# design.net
KiCad netlist of a schematic drawn in Altium Designer
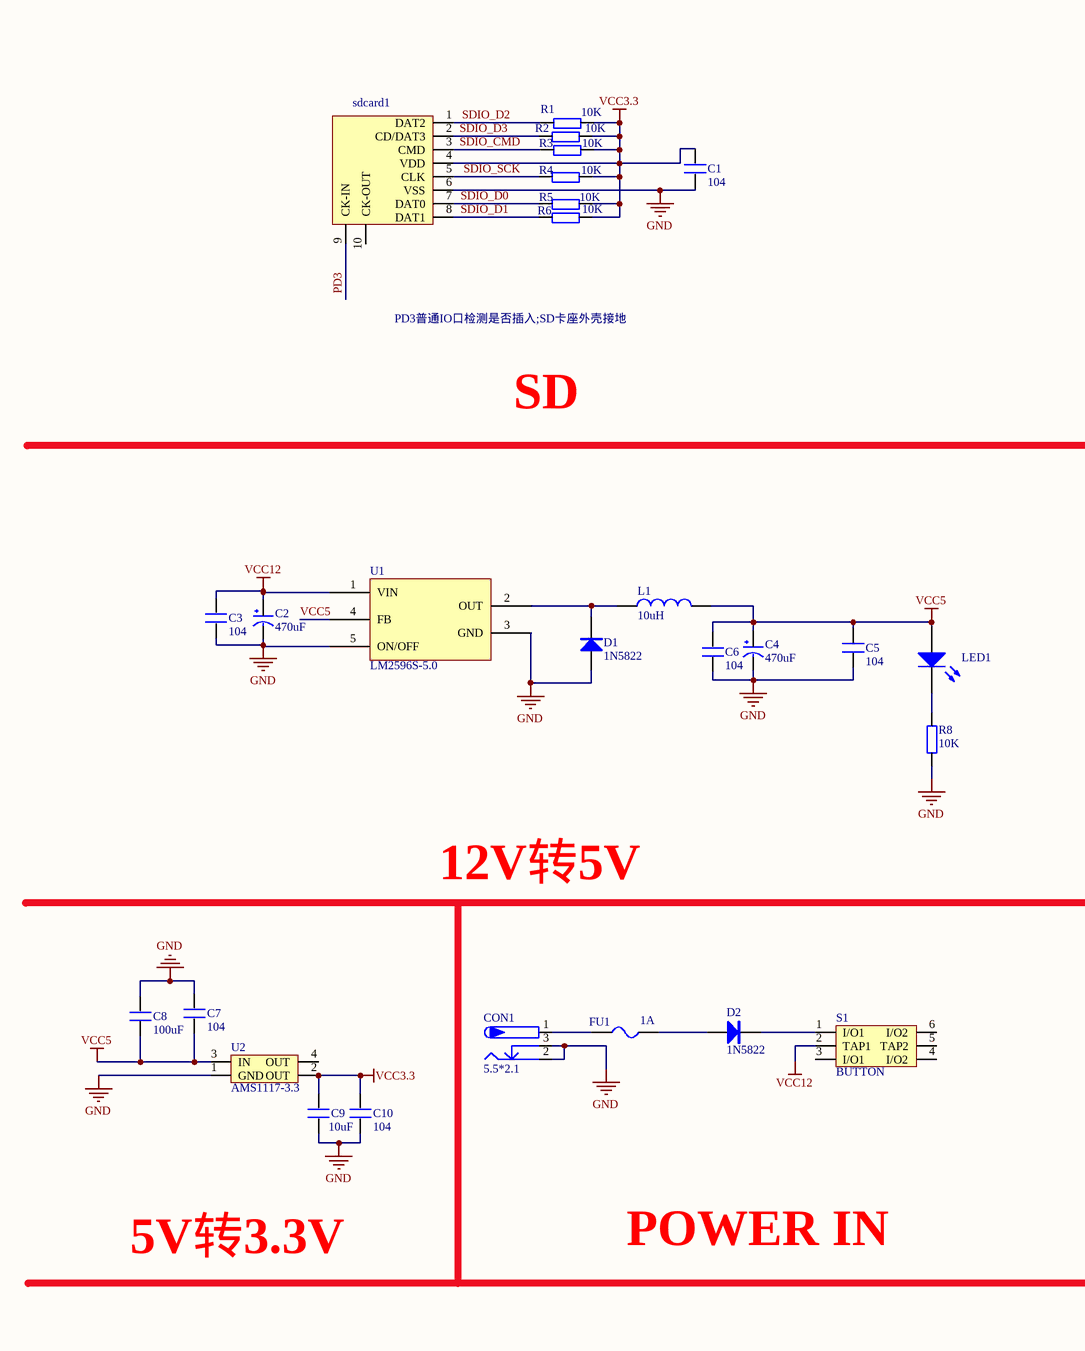
[diagram p0: 门禁改.SchDoc, top left]
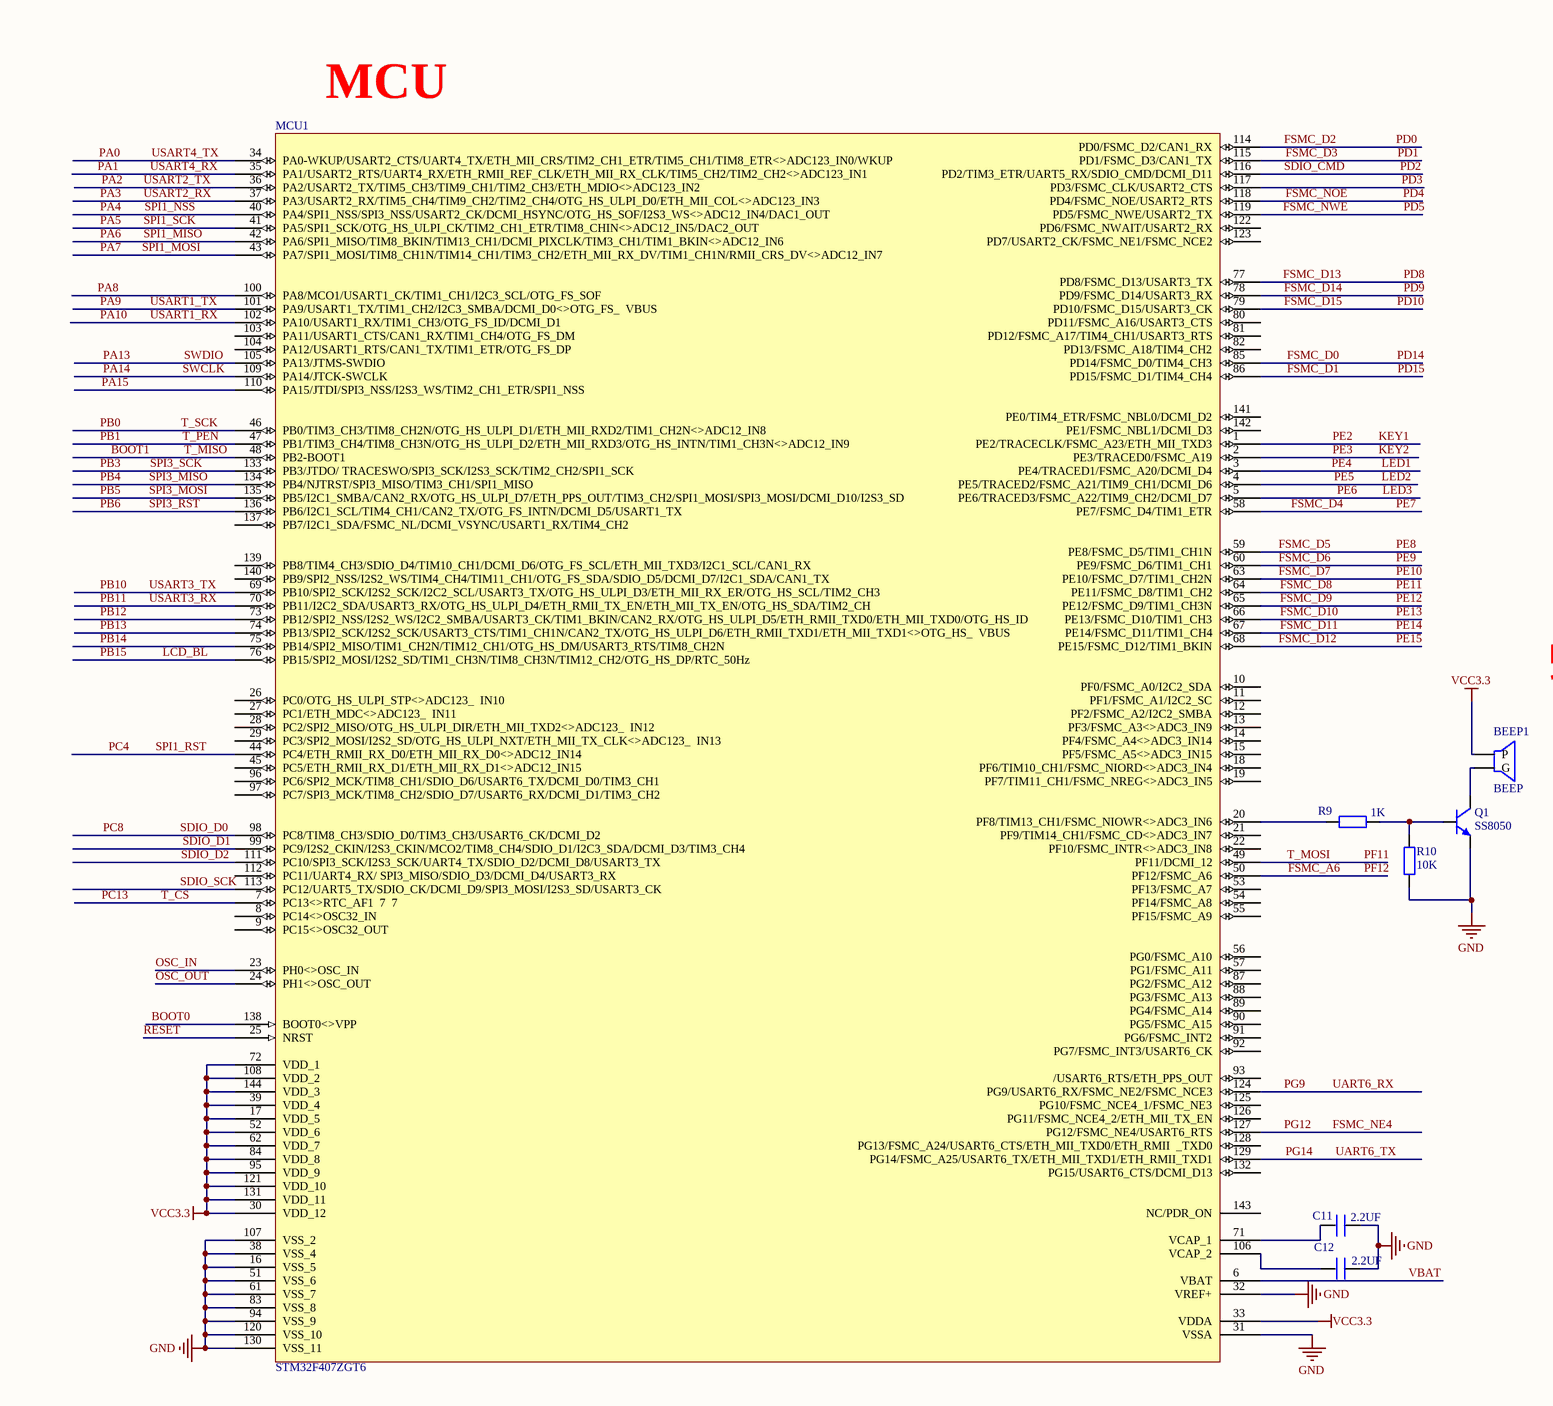
[diagram p1: 门禁改.SchDoc, top middle]
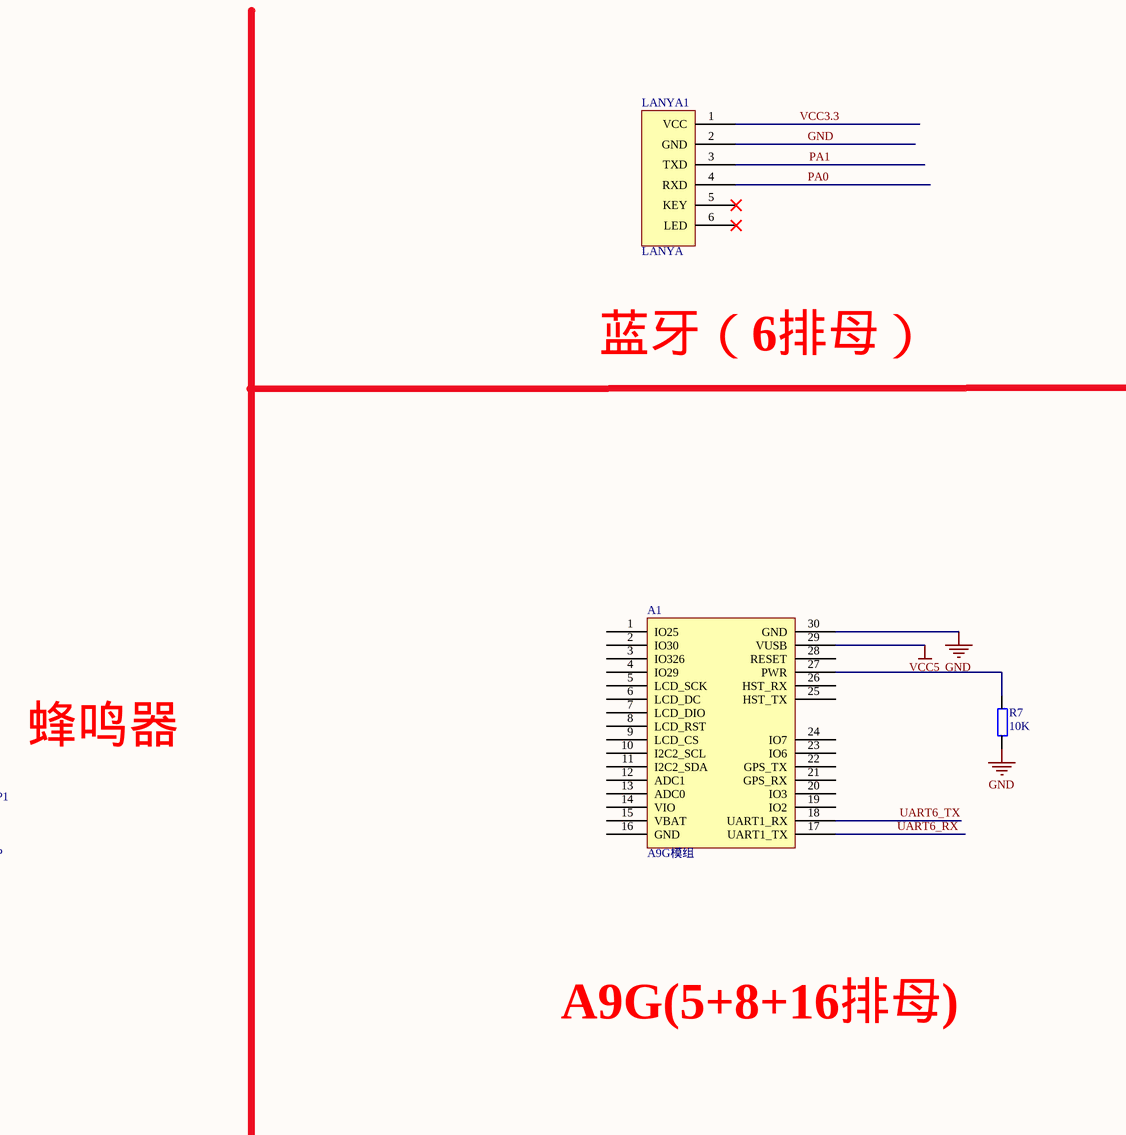
[diagram p2: 门禁改.SchDoc, top right]
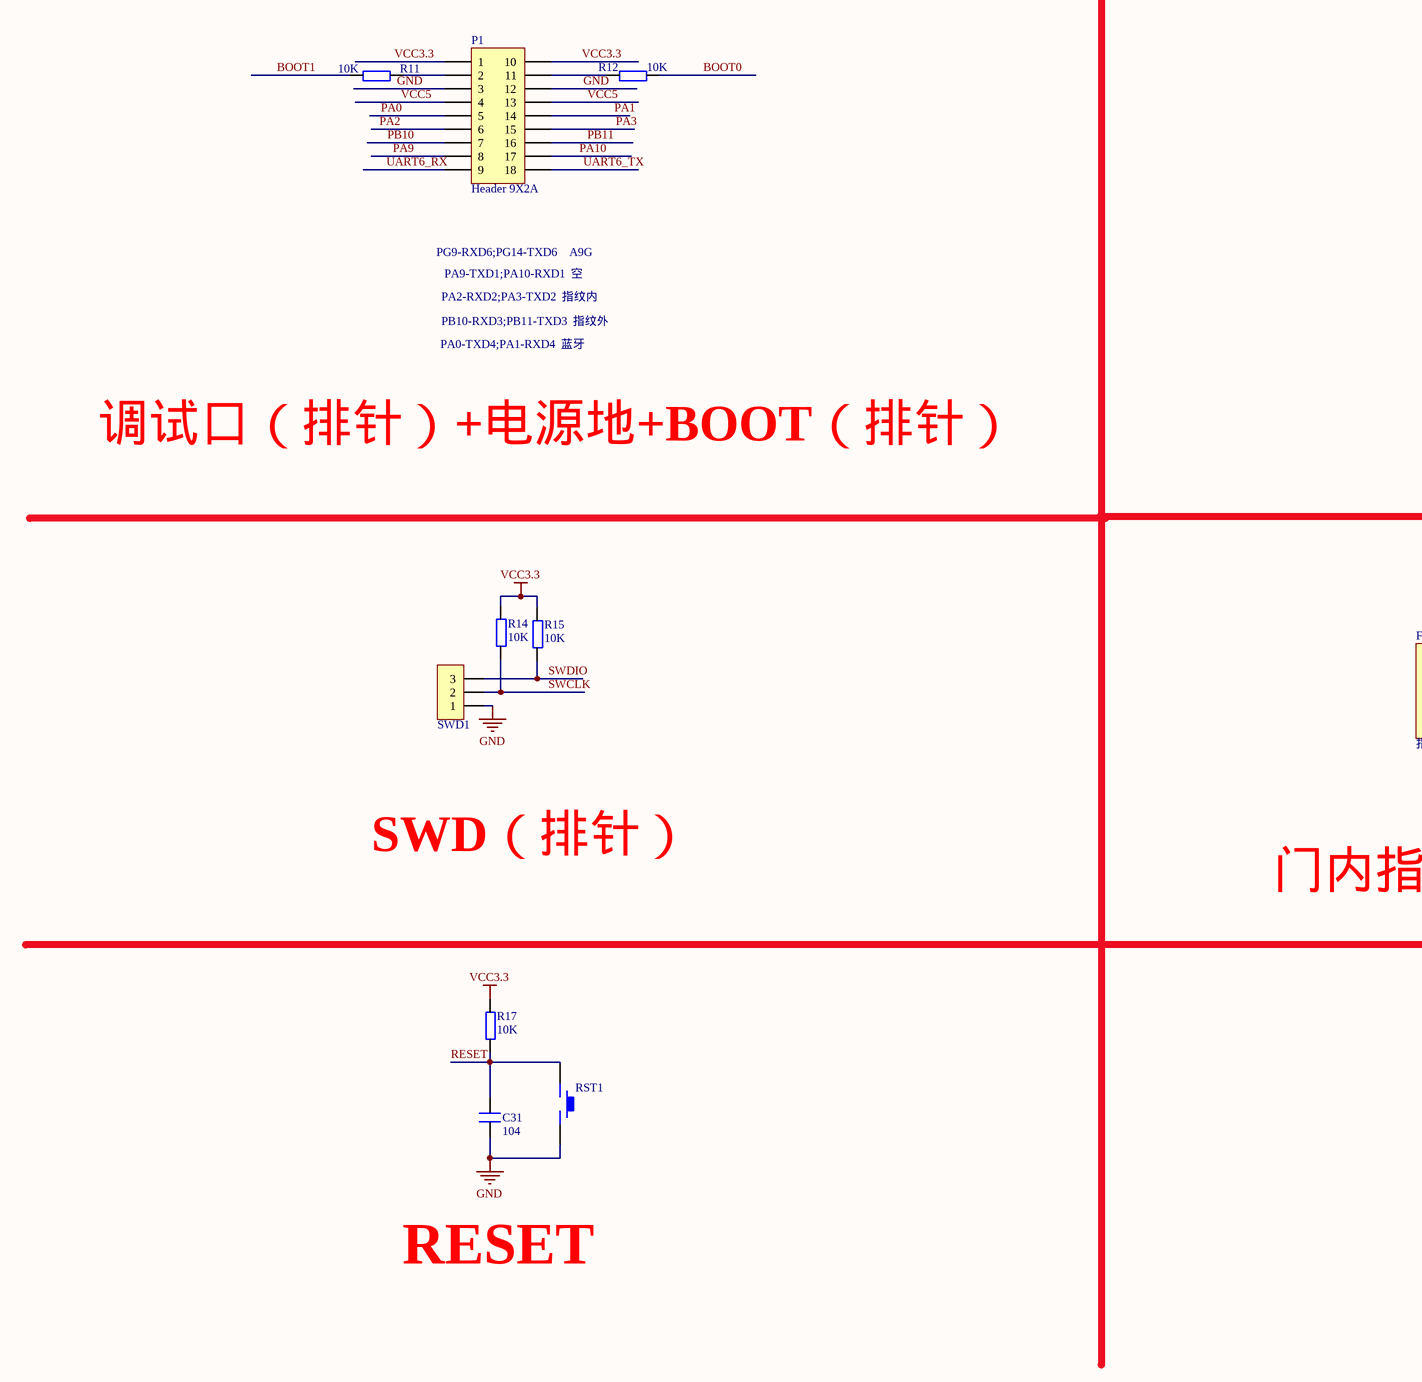
[diagram p3: 门禁改.SchDoc, bottom left]
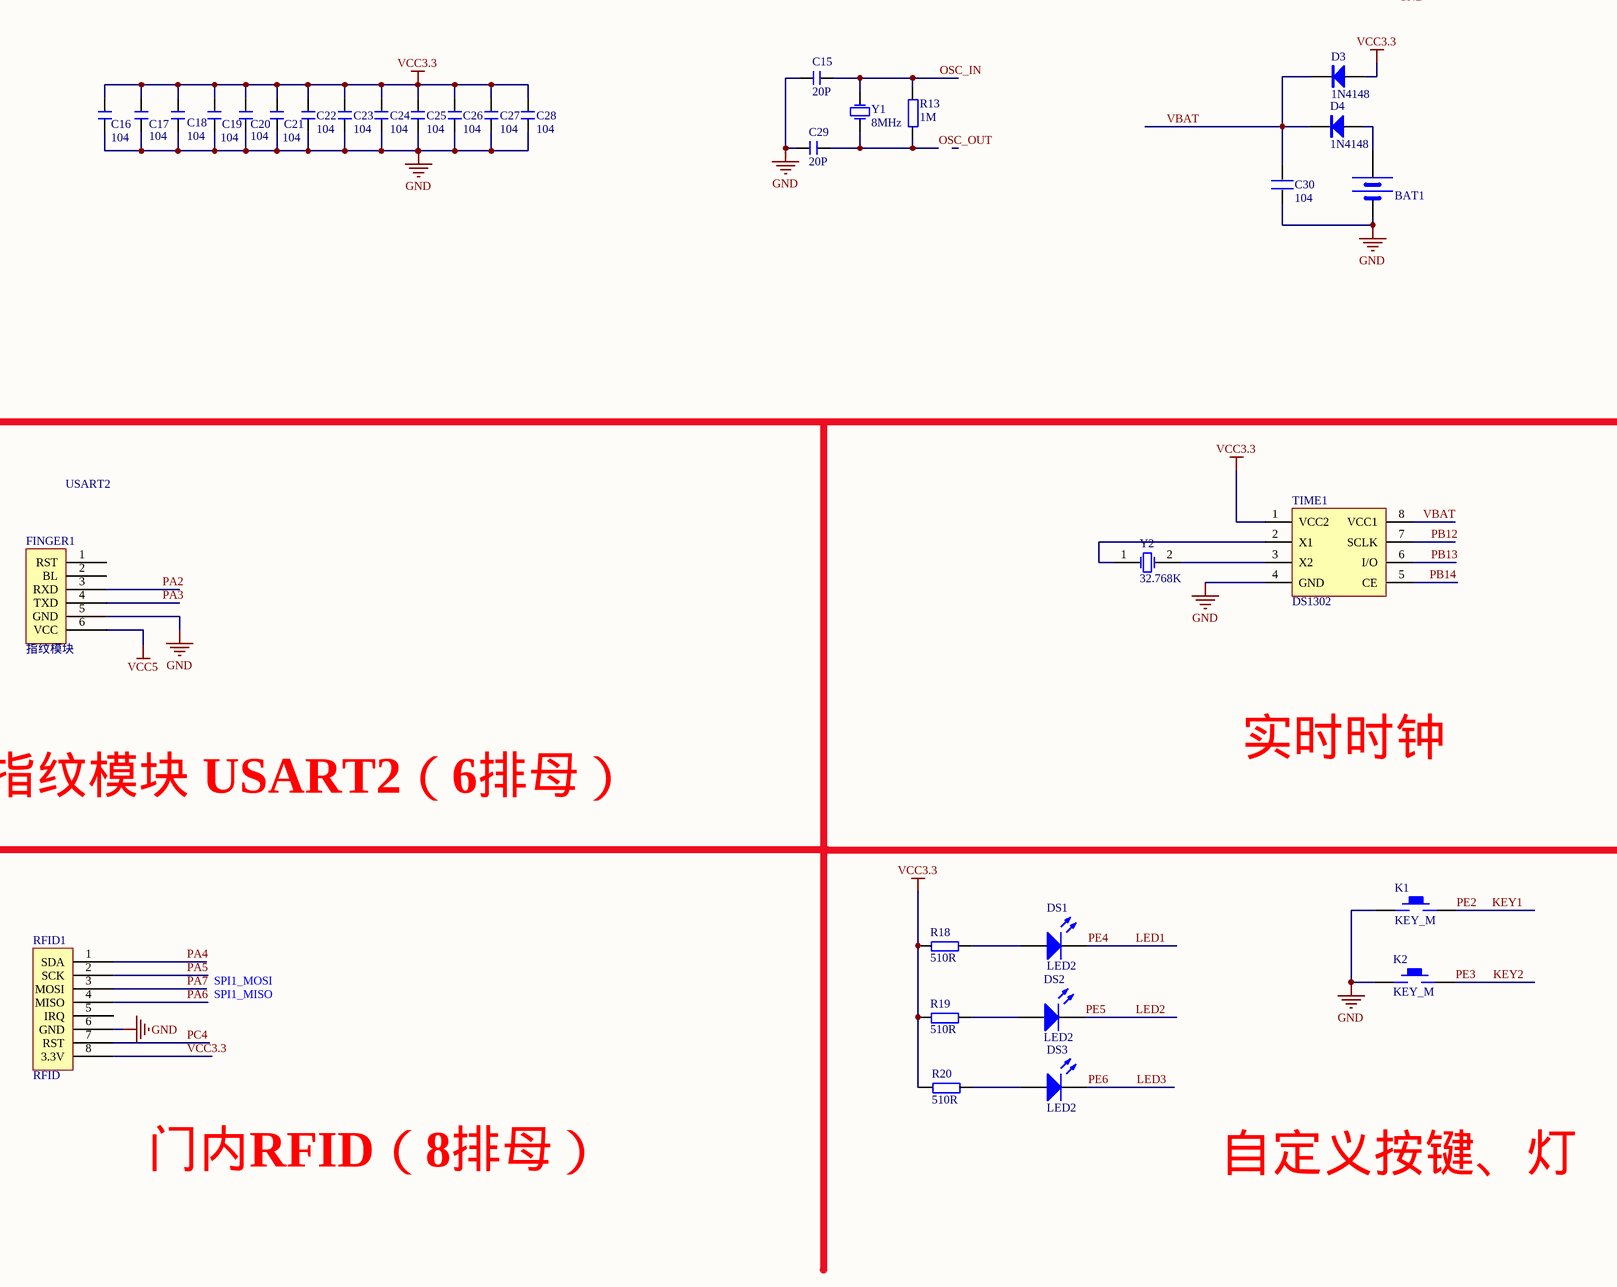
[diagram p4: 门禁改.SchDoc, bottom middle]
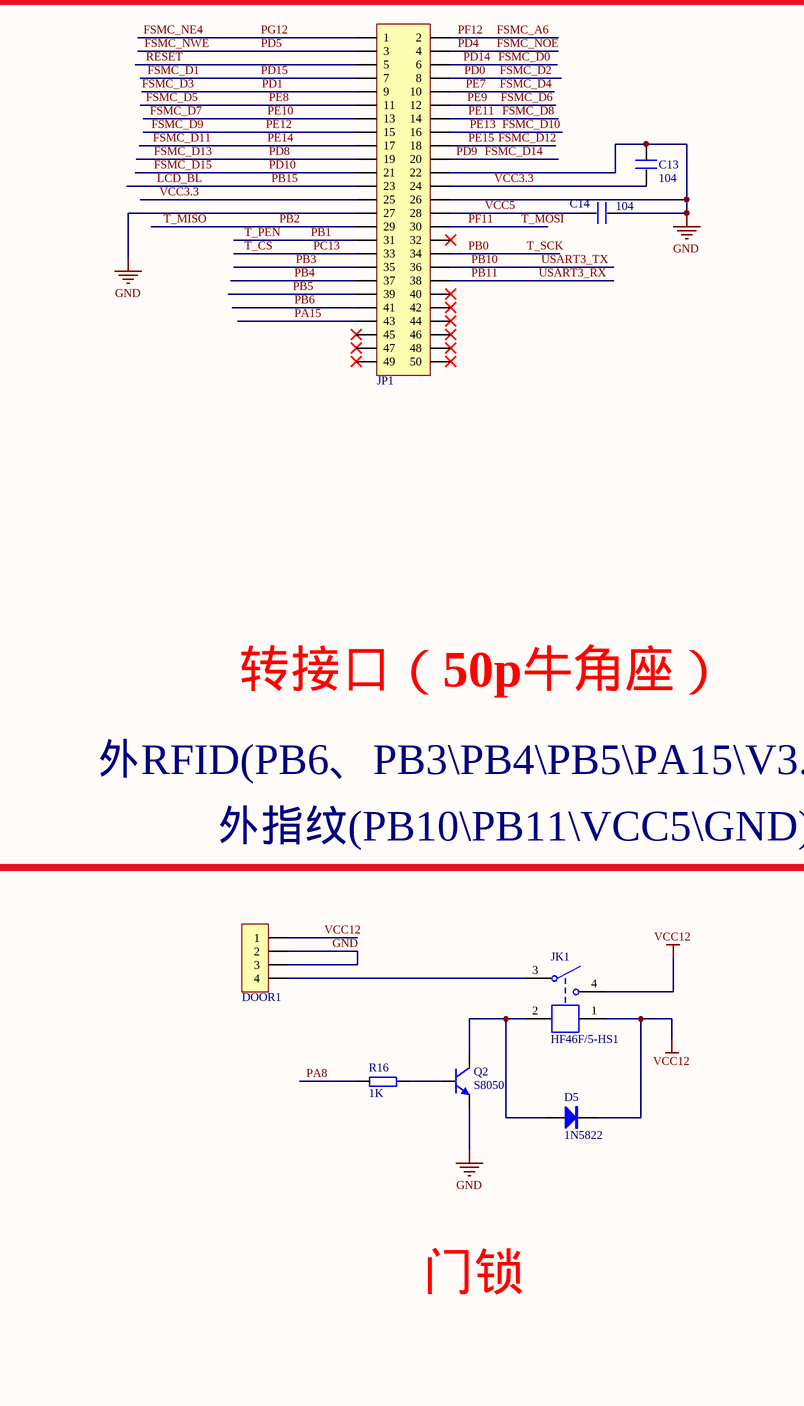
[diagram p5: 门禁改.SchDoc, bottom right]

(export (version "E")
  (design (tool "Eeschema 10.0.6"))
  (components
    (comp (ref "A1") (value "A9G模组") (footprint "A9G") (libsource (lib "A9G模组") (part "A9G模组")))
    (comp (ref "BAT1") (value "BATT") (footprint "BATMAX") (libsource (lib "门禁系统") (part "BAT")))
    (comp (ref "BEEP1") (value "BEEP") (footprint "BUZZ") (libsource (lib "门禁系统") (part "BEEP")))
    (comp (ref "C1") (value "104") (footprint "0805") (libsource (lib "Explorer STM32F407封装库") (part "C")))
    (comp (ref "C2") (value "470uF") (footprint "CM F(10*10.2)") (libsource (lib "门禁系统") (part "CAP")))
    (comp (ref "C3") (value "104") (footprint "0805") (libsource (lib "门禁系统") (part "C")))
    (comp (ref "C4") (value "470uF") (footprint "CM F(10*10.2)") (libsource (lib "门禁系统") (part "CAP")))
    (comp (ref "C5") (value "104") (footprint "0805") (libsource (lib "门禁系统") (part "C")))
    (comp (ref "C6") (value "104") (footprint "0805") (libsource (lib "门禁系统") (part "C")))
    (comp (ref "C7") (value "104") (footprint "0603P") (libsource (lib "Explorer STM32F407封装库") (part "C")))
    (comp (ref "C8")
      (value "100uF")
      (footprint "CM D(6.3*7.7)")
      (libsource (lib "Explorer STM32F407封装库") (part "C"))
    )
    (comp (ref "C9") (value "10uF") (footprint "0603P") (libsource (lib "Explorer STM32F407封装库") (part "C")))
    (comp (ref "C10") (value "104") (footprint "0603P") (libsource (lib "Explorer STM32F407封装库") (part "C")))
    (comp (ref "C11")
      (value "2.2UF")
      (footprint "0805")
      (libsource (lib "Explorer STM32F407封装库_SCH") (part "C_1"))
    )
    (comp (ref "C12")
      (value "2.2UF")
      (footprint "0805")
      (libsource (lib "Explorer STM32F407封装库_SCH") (part "C_1"))
    )
    (comp (ref "C13") (value "104") (footprint "0805") (libsource (lib "Explorer STM32F407封装库") (part "C")))
    (comp (ref "C14") (value "104") (footprint "0805") (libsource (lib "Explorer STM32F407封装库") (part "C")))
    (comp (ref "C15")
      (value "20P")
      (footprint "0805")
      (description "无极性贴片电容")
      (fields (field (name "版权归属") "源创客"))
      (libsource (lib "3.1   - 电阻-电容-电感") (part "C"))
    )
    (comp (ref "C16")
      (value "104")
      (footprint "0805")
      (description "无极性贴片电容")
      (fields (field (name "版权归属") "源创客"))
      (libsource (lib "3.1   - 电阻-电容-电感") (part "C"))
    )
    (comp (ref "C17")
      (value "104")
      (footprint "0805")
      (description "无极性贴片电容")
      (fields (field (name "版权归属") "源创客"))
      (libsource (lib "3.1   - 电阻-电容-电感") (part "C"))
    )
    (comp (ref "C18")
      (value "104")
      (footprint "0805")
      (description "无极性贴片电容")
      (fields (field (name "版权归属") "源创客"))
      (libsource (lib "3.1   - 电阻-电容-电感") (part "C"))
    )
    (comp (ref "C19")
      (value "104")
      (footprint "0805")
      (description "无极性贴片电容")
      (fields (field (name "版权归属") "源创客"))
      (libsource (lib "3.1   - 电阻-电容-电感") (part "C"))
    )
    (comp (ref "C20")
      (value "104")
      (footprint "0805")
      (description "无极性贴片电容")
      (fields (field (name "版权归属") "源创客"))
      (libsource (lib "3.1   - 电阻-电容-电感") (part "C"))
    )
    (comp (ref "C21")
      (value "104")
      (footprint "0805")
      (description "无极性贴片电容")
      (fields (field (name "版权归属") "源创客"))
      (libsource (lib "3.1   - 电阻-电容-电感") (part "C"))
    )
    (comp (ref "C22")
      (value "104")
      (footprint "0805")
      (description "无极性贴片电容")
      (fields (field (name "版权归属") "源创客"))
      (libsource (lib "3.1   - 电阻-电容-电感") (part "C"))
    )
    (comp (ref "C23")
      (value "104")
      (footprint "0805")
      (description "无极性贴片电容")
      (fields (field (name "版权归属") "源创客"))
      (libsource (lib "3.1   - 电阻-电容-电感") (part "C"))
    )
    (comp (ref "C24")
      (value "104")
      (footprint "0805")
      (description "无极性贴片电容")
      (fields (field (name "版权归属") "源创客"))
      (libsource (lib "3.1   - 电阻-电容-电感") (part "C"))
    )
    (comp (ref "C25")
      (value "104")
      (footprint "0805")
      (description "无极性贴片电容")
      (fields (field (name "版权归属") "源创客"))
      (libsource (lib "3.1   - 电阻-电容-电感") (part "C"))
    )
    (comp (ref "C26")
      (value "104")
      (footprint "0805")
      (description "无极性贴片电容")
      (fields (field (name "版权归属") "源创客"))
      (libsource (lib "3.1   - 电阻-电容-电感") (part "C"))
    )
    (comp (ref "C27")
      (value "104")
      (footprint "0805")
      (description "无极性贴片电容")
      (fields (field (name "版权归属") "源创客"))
      (libsource (lib "3.1   - 电阻-电容-电感") (part "C"))
    )
    (comp (ref "C28")
      (value "104")
      (footprint "0805")
      (description "无极性贴片电容")
      (fields (field (name "版权归属") "源创客"))
      (libsource (lib "3.1   - 电阻-电容-电感") (part "C"))
    )
    (comp (ref "C29")
      (value "20P")
      (footprint "0805")
      (description "无极性贴片电容")
      (fields (field (name "版权归属") "源创客"))
      (libsource (lib "3.1   - 电阻-电容-电感") (part "C"))
    )
    (comp (ref "C30") (value "104") (footprint "0805") (libsource (lib "门禁") (part "C")))
    (comp (ref "C31")
      (value "104")
      (footprint "0805")
      (libsource (lib "Explorer STM32F407封装库_SCH") (part "C"))
    )
    (comp (ref "CON1")
      (value "5.5*2.1")
      (footprint "DC-005")
      (description "低压电源接口")
      (fields (field (name "版权归属") "源创客"))
      (libsource (lib "4.1   - 接口类") (part "P-DC"))
    )
    (comp (ref "D1")
      (value "1N5822")
      (footprint "DIODE_3*5.3")
      (description "高速开关二极管")
      (fields (field (name "版权归属") "源创客"))
      (libsource (lib "8.1   - 二极管-整流桥") (part "1N4148"))
    )
    (comp (ref "D2")
      (value "1N5822")
      (footprint "DIODE_3*5.3")
      (description "高速开关二极管")
      (fields (field (name "版权归属") "源创客"))
      (libsource (lib "8.1   - 二极管-整流桥") (part "1N4148"))
    )
    (comp (ref "D3")
      (value "1N4148")
      (footprint "DIODE_3*5.3")
      (description "高速开关二极管")
      (fields (field (name "版权归属") "源创客"))
      (libsource (lib "门禁") (part "1N4148"))
    )
    (comp (ref "D4")
      (value "1N4148")
      (footprint "DIODE_3*5.3")
      (description "高速开关二极管")
      (fields (field (name "版权归属") "源创客"))
      (libsource (lib "门禁") (part "1N4148"))
    )
    (comp (ref "D5")
      (value "1N5822")
      (footprint "DIODE_3*5.3")
      (description "高速开关二极管")
      (fields (field (name "版权归属") "源创客"))
      (libsource (lib "8.1   - 二极管-整流桥") (part "1N4148"))
    )
    (comp (ref "DOOR1")
      (value "HDR-1X4")
      (footprint "XH2.54-WI-4P")
      (description "4P接插件")
      (fields (field (name "版权归属") "源创客"))
      (libsource (lib "4.5   - 接插件-脚距2.54") (part "Header 4"))
    )
    (comp (ref "DS1")
      (value "LED2")
      (footprint "SMDLED")
      (description "Typical RED, GREEN, YELLOW, AMBER GaAs LED")
      (fields (field (name "PUBLISHER") "*"))
      (libsource (lib "Explorer STM32F407封装库_SCH") (part "LED2"))
    )
    (comp (ref "DS2")
      (value "LED2")
      (footprint "SMDLED")
      (description "Typical RED, GREEN, YELLOW, AMBER GaAs LED")
      (fields (field (name "PUBLISHER") "*"))
      (libsource (lib "Explorer STM32F407封装库_SCH") (part "LED2"))
    )
    (comp (ref "DS3")
      (value "LED2")
      (footprint "SMDLED")
      (description "Typical RED, GREEN, YELLOW, AMBER GaAs LED")
      (fields (field (name "PUBLISHER") "*"))
      (libsource (lib "Explorer STM32F407封装库_SCH") (part "LED2"))
    )
    (comp (ref "FINGER1") (value "指纹模块") (footprint "指纹") (libsource (lib "Schlib1") (part "指纹模块")))
    (comp (ref "FU1")
      (value "1A")
      (footprint "FU 1812")
      (description "贴片保险丝")
      (fields (field (name "版权归属") "源创客"))
      (libsource (lib "10.1 - 保险丝-晶振") (part "FU"))
    )
    (comp (ref "JK1")
      (value "HF46F/5-HS1")
      (footprint "HF46-xx-HS1")
      (description "5V一组常开")
      (fields (field (name "版权归属") "源创客"))
      (libsource (lib "7.1   - 继电器") (part "HF46F/5-HS1"))
    )
    (comp (ref "JP1")
      (value "Header 2X25")
      (footprint "IDC2.54-LI-2x25P")
      (description "25*2P接插件")
      (fields (field (name "版权归属") "源创客"))
      (libsource (lib "4.5   - 接插件-脚距2.54") (part "Header 25X2"))
    )
    (comp (ref "K1")
      (value "KEY_M")
      (footprint "KEY_M")
      (libsource (lib "Explorer STM32F407封装库_SCH") (part "KEY_M"))
    )
    (comp (ref "K2")
      (value "KEY_M")
      (footprint "KEY_M")
      (libsource (lib "Explorer STM32F407封装库_SCH") (part "KEY_M"))
    )
    (comp (ref "L1")
      (value "10uH")
      (footprint "0805")
      (description "小功率贴片电感")
      (fields (field (name "版权归属") "源创客"))
      (libsource (lib "3.1   - 电阻-电容-电感") (part "L"))
    )
    (comp (ref "LANYA1") (value "LANYA") (footprint "蓝牙") (libsource (lib "Schlib1") (part "蓝牙模块")))
    (comp (ref "LED1")
      (value "LED1")
      (footprint "SMDLED")
      (description "Typical RED, GREEN, YELLOW, AMBER GaAs LED")
      (fields (field (name "PUBLISHER") "Altium Limited"))
      (libsource (lib "门禁系统") (part "LED2"))
    )
    (comp (ref "MCU1")
      (value "STM32F407ZGT6")
      (footprint "LQFP144")
      (libsource (lib "STM32F407 ") (part "STM32F407ZGT6"))
    )
    (comp (ref "P1")
      (value "Header 9X2A")
      (footprint "HDR2X9_CEN")
      (description "Header, 9-Pin, Dual row")
      (fields (field (name "PUBLISHER") "Altium Limited"))
      (libsource (lib "Miscellaneous Connectors") (part "Header 9X2A"))
    )
    (comp (ref "Q1")
      (value "SS8050")
      (footprint "SOT23-3N")
      (description "高频放大-NPN型")
      (fields (field (name "版权归属") "源创客"))
      (libsource (lib "6.2   - 三极管") (part "8050-SMD"))
    )
    (comp (ref "Q2")
      (value "S8050")
      (footprint "SOT23-3N")
      (description "高频放大-NPN型")
      (fields (field (name "版权归属") "源创客"))
      (libsource (lib "6.2   - 三极管") (part "8050-SMD"))
    )
    (comp (ref "R1") (value "10K") (footprint "0805") (libsource (lib "Explorer STM32F407封装库") (part "R")))
    (comp (ref "R2") (value "10K") (footprint "0805") (libsource (lib "Explorer STM32F407封装库") (part "R")))
    (comp (ref "R3") (value "10K") (footprint "0805") (libsource (lib "Explorer STM32F407封装库") (part "R")))
    (comp (ref "R4") (value "10K") (footprint "0805") (libsource (lib "Explorer STM32F407封装库") (part "R")))
    (comp (ref "R5") (value "10K") (footprint "0805") (libsource (lib "Explorer STM32F407封装库") (part "R")))
    (comp (ref "R6") (value "10K") (footprint "0805") (libsource (lib "Explorer STM32F407封装库") (part "R")))
    (comp (ref "R7") (value "10K") (footprint "0805") (libsource (lib "门禁") (part "R")))
    (comp (ref "R8") (value "10K") (footprint "0805") (libsource (lib "门禁系统") (part "R")))
    (comp (ref "R9")
      (value "1K")
      (footprint "0805")
      (description "贴片电阻")
      (fields (field (name "版权归属") "源创客"))
      (libsource (lib "3.1   - 电阻-电容-电感") (part "R"))
    )
    (comp (ref "R10")
      (value "10K")
      (footprint "0805")
      (description "贴片电阻")
      (fields (field (name "版权归属") "源创客"))
      (libsource (lib "3.1   - 电阻-电容-电感") (part "R"))
    )
    (comp (ref "R11") (value "10K") (footprint "0805") (libsource (lib "Explorer STM32F407封装库") (part "R")))
    (comp (ref "R12")
      (value "10K")
      (footprint "0805")
      (libsource (lib "Explorer STM32F407封装库_SCH") (part "R"))
    )
    (comp (ref "R13") (value "1M") (footprint "0805") (libsource (lib "门禁系统") (part "R")))
    (comp (ref "R14") (value "10K") (footprint "0805") (libsource (lib "WarShip V3 STM32103封装库") (part "R")))
    (comp (ref "R15") (value "10K") (footprint "0805") (libsource (lib "WarShip V3 STM32103封装库") (part "R")))
    (comp (ref "R16")
      (value "1K")
      (footprint "0805")
      (libsource (lib "Explorer STM32F407封装库_SCH") (part "R"))
    )
    (comp (ref "R17")
      (value "10K")
      (footprint "0805")
      (libsource (lib "Explorer STM32F407封装库_SCH") (part "R"))
    )
    (comp (ref "R18")
      (value "510R")
      (footprint "0805")
      (libsource (lib "Explorer STM32F407封装库_SCH") (part "R"))
    )
    (comp (ref "R19")
      (value "510R")
      (footprint "0805")
      (libsource (lib "Explorer STM32F407封装库_SCH") (part "R"))
    )
    (comp (ref "R20")
      (value "510R")
      (footprint "0805")
      (libsource (lib "Explorer STM32F407封装库_SCH") (part "R"))
    )
    (comp (ref "RFID1") (value "RFID") (footprint "RFID") (libsource (lib "Schlib1") (part "RC522")))
    (comp (ref "RST1") (value "~") (footprint "KEY_M") (libsource (lib "") (part "KEY_M_1")))
    (comp (ref "S1") (value "BUTTON") (footprint "BTN8.5*8.5") (libsource (lib "门禁系统") (part "BUTTON")))
    (comp (ref "sdcard1")
      (value "sdIO-sdcard")
      (footprint "sdcard_2")
      (libsource (lib "门禁系统") (part "sdIO-sdcard"))
    )
    (comp (ref "SWD1")
      (value "HDR-1X3")
      (footprint "HDR2.54-LI-3P")
      (description "3P接插件")
      (fields (field (name "版权归属") "源创客"))
      (libsource (lib "4.10 - 接插件-脚距5.08") (part "Header 3"))
    )
    (comp (ref "TIME1")
      (value "DS1302")
      (footprint "SOP8_N")
      (description "实时时钟芯片")
      (fields (field (name "版权归属") "源创客"))
      (libsource (lib "1.1   - IC芯片") (part "DS1302"))
    )
    (comp (ref "U1")
      (value "LM2596S-5.0")
      (footprint "TO263-5A")
      (description "LM2576S-5.0")
      (libsource (lib "Schlib1") (part "Component_1"))
    )
    (comp (ref "U2") (value "AMS1117-3.3") (footprint "AMS1117") (libsource (lib "门禁系统") (part "AMS1117")))
    (comp (ref "Y1")
      (value "8MHz")
      (footprint "XTAL_T")
      (description "Crystal Oscillator")
      (fields (field (name "PUBLISHER") "Altium Limited"))
      (libsource (lib "门禁系统") (part "XTAL_2"))
    )
    (comp (ref "Y2")
      (value "32.768K")
      (footprint "XTAL32")
      (description "Crystal Oscillator")
      (fields (field (name "PUBLISHER") "Altium Limited"))
      (libsource (lib "门禁系统") (part "XTAL_1"))
    )
  )
  (nets
    (net (code "2") (name "/BOOT0") (class "Default")
      (node (ref "MCU1") (pin "138") (pinfunction "BOOT0<>VPP_138") (pintype "input"))
      (node (ref "R12") (pin "2") (pintype "passive"))
    )
    (net (code "3") (name "/BOOT1") (class "Default")
      (node (ref "JP1") (pin "29") (pinfunction "29_29") (pintype "passive"))
      (node (ref "MCU1") (pin "48") (pinfunction "PB2-BOOT1_48") (pintype "bidirectional"))
      (node (ref "R11") (pin "1") (pintype "passive"))
    )
    (net (code "4") (name "/FSMC_A6") (class "Default")
      (node (ref "JP1") (pin "2") (pinfunction "2_2") (pintype "passive"))
      (node (ref "MCU1") (pin "50") (pinfunction "PF12/FSMC_A6_50") (pintype "bidirectional"))
    )
    (net (code "5") (name "/FSMC_D0") (class "Default")
      (node (ref "JP1") (pin "6") (pinfunction "6_6") (pintype "passive"))
      (node (ref "MCU1") (pin "85") (pinfunction "PD14/FSMC_D0/TIM4_CH3_85") (pintype "bidirectional"))
    )
    (net (code "6") (name "/FSMC_D1") (class "Default")
      (node (ref "JP1") (pin "7") (pinfunction "7_7") (pintype "passive"))
      (node (ref "MCU1") (pin "86") (pinfunction "PD15/FSMC_D1/TIM4_CH4_86") (pintype "bidirectional"))
    )
    (net (code "7") (name "/FSMC_D2") (class "Default")
      (node (ref "JP1") (pin "8") (pinfunction "8_8") (pintype "passive"))
      (node (ref "MCU1") (pin "114") (pinfunction "PD0/FSMC_D2/CAN1_RX_114") (pintype "bidirectional"))
    )
    (net (code "8") (name "/FSMC_D3") (class "Default")
      (node (ref "JP1") (pin "9") (pinfunction "9_9") (pintype "passive"))
      (node (ref "MCU1") (pin "115") (pinfunction "PD1/FSMC_D3/CAN1_TX_115") (pintype "bidirectional"))
    )
    (net (code "9") (name "/FSMC_D4") (class "Default")
      (node (ref "JP1") (pin "10") (pinfunction "10_10") (pintype "passive"))
      (node (ref "MCU1") (pin "58") (pinfunction "PE7/FSMC_D4/TIM1_ETR_58") (pintype "bidirectional"))
    )
    (net (code "10") (name "/FSMC_D5") (class "Default")
      (node (ref "JP1") (pin "11") (pinfunction "11_11") (pintype "passive"))
      (node (ref "MCU1") (pin "59") (pinfunction "PE8/FSMC_D5/TIM1_CH1N_59") (pintype "bidirectional"))
    )
    (net (code "11") (name "/FSMC_D6") (class "Default")
      (node (ref "JP1") (pin "12") (pinfunction "12_12") (pintype "passive"))
      (node (ref "MCU1") (pin "60") (pinfunction "PE9/FSMC_D6/TIM1_CH1_60") (pintype "bidirectional"))
    )
    (net (code "12") (name "/FSMC_D7") (class "Default")
      (node (ref "JP1") (pin "13") (pinfunction "13_13") (pintype "passive"))
      (node (ref "MCU1") (pin "63") (pinfunction "PE10/FSMC_D7/TIM1_CH2N_63") (pintype "bidirectional"))
    )
    (net (code "13") (name "/FSMC_D8") (class "Default")
      (node (ref "JP1") (pin "14") (pinfunction "14_14") (pintype "passive"))
      (node (ref "MCU1") (pin "64") (pinfunction "PE11/FSMC_D8/TIM1_CH2_64") (pintype "bidirectional"))
    )
    (net (code "14") (name "/FSMC_D9") (class "Default")
      (node (ref "JP1") (pin "15") (pinfunction "15_15") (pintype "passive"))
      (node (ref "MCU1") (pin "65") (pinfunction "PE12/FSMC_D9/TIM1_CH3N_65") (pintype "bidirectional"))
    )
    (net (code "15") (name "/FSMC_D10") (class "Default")
      (node (ref "JP1") (pin "16") (pinfunction "16_16") (pintype "passive"))
      (node (ref "MCU1") (pin "66") (pinfunction "PE13/FSMC_D10/TIM1_CH3_66") (pintype "bidirectional"))
    )
    (net (code "16") (name "/FSMC_D11") (class "Default")
      (node (ref "JP1") (pin "17") (pinfunction "17_17") (pintype "passive"))
      (node (ref "MCU1") (pin "67") (pinfunction "PE14/FSMC_D11/TIM1_CH4_67") (pintype "bidirectional"))
    )
    (net (code "17") (name "/FSMC_D12") (class "Default")
      (node (ref "JP1") (pin "18") (pinfunction "18_18") (pintype "passive"))
      (node (ref "MCU1") (pin "68") (pinfunction "PE15/FSMC_D12/TIM1_BKIN_68") (pintype "bidirectional"))
    )
    (net (code "18") (name "/FSMC_D13") (class "Default")
      (node (ref "JP1") (pin "19") (pinfunction "19_19") (pintype "passive"))
      (node (ref "MCU1") (pin "77") (pinfunction "PD8/FSMC_D13/USART3_TX_77") (pintype "bidirectional"))
    )
    (net (code "19") (name "/FSMC_D14") (class "Default")
      (node (ref "JP1") (pin "20") (pinfunction "20_20") (pintype "passive"))
      (node (ref "MCU1") (pin "78") (pinfunction "PD9/FSMC_D14/USART3_RX_78") (pintype "bidirectional"))
    )
    (net (code "20") (name "/FSMC_D15") (class "Default")
      (node (ref "JP1") (pin "21") (pinfunction "21_21") (pintype "passive"))
      (node (ref "MCU1") (pin "79") (pinfunction "PD10/FSMC_D15/USART3_CK_79") (pintype "bidirectional"))
    )
    (net (code "21") (name "/FSMC_NE4") (class "Default")
      (node (ref "JP1") (pin "1") (pinfunction "1_1") (pintype "passive"))
      (node (ref "MCU1") (pin "127") (pinfunction "PG12/FSMC_NE4/USART6_RTS_127") (pintype "bidirectional"))
    )
    (net (code "22") (name "/FSMC_NOE") (class "Default")
      (node (ref "JP1") (pin "4") (pinfunction "4_4") (pintype "passive"))
      (node (ref "MCU1") (pin "118") (pinfunction "PD4/FSMC_NOE/USART2_RTS_118") (pintype "bidirectional"))
    )
    (net (code "23") (name "/FSMC_NWE") (class "Default")
      (node (ref "JP1") (pin "3") (pinfunction "3_3") (pintype "passive"))
      (node (ref "MCU1") (pin "119") (pinfunction "PD5/FSMC_NWE/USART2_TX_119") (pintype "bidirectional"))
    )
    (net (code "24") (name "/KEY1") (class "Default")
      (node (ref "K1") (pin "2") (pinfunction "2_2") (pintype "passive"))
      (node (ref "MCU1") (pin "1") (pinfunction "PE2/TRACECLK/FSMC_A23/ETH_MII_TXD3_1") (pintype "bidirectional"))
    )
    (net (code "25") (name "/KEY2") (class "Default")
      (node (ref "K2") (pin "2") (pinfunction "2_2") (pintype "passive"))
      (node (ref "MCU1") (pin "2") (pinfunction "PE3/TRACED0/FSMC_A19_2") (pintype "bidirectional"))
    )
    (net (code "26") (name "/LCD_BL") (class "Default")
      (node (ref "JP1") (pin "23") (pinfunction "23_23") (pintype "passive"))
      (node (ref "MCU1") (pin "76") (pinfunction "PB15/SPI2_MOSI/I2S2_SD/TIM1_CH3N/TIM8_CH3N/TIM12_CH2/OTG_HS_DP/RTC_50Hz_76") (pintype "bidirectional"))
    )
    (net (code "27") (name "/LED1") (class "Default")
      (node (ref "DS1") (pin "2") (pinfunction "K_2") (pintype "passive"))
      (node (ref "MCU1") (pin "3") (pinfunction "PE4/TRACED1/FSMC_A20/DCMI_D4_3") (pintype "bidirectional"))
    )
    (net (code "28") (name "/LED2") (class "Default")
      (node (ref "DS2") (pin "2") (pinfunction "K_2") (pintype "passive"))
      (node (ref "MCU1") (pin "4") (pinfunction "PE5/TRACED2/FSMC_A21/TIM9_CH1/DCMI_D6_4") (pintype "bidirectional"))
    )
    (net (code "29") (name "/LED3") (class "Default")
      (node (ref "DS3") (pin "2") (pinfunction "K_2") (pintype "passive"))
      (node (ref "MCU1") (pin "5") (pinfunction "PE6/TRACED3/FSMC_A22/TIM9_CH2/DCMI_D7_5") (pintype "bidirectional"))
    )
    (net (code "30") (name "/OSC_IN") (class "Default")
      (node (ref "C15") (pin "1") (pinfunction "1_1") (pintype "passive"))
      (node (ref "MCU1") (pin "23") (pinfunction "PH0<>OSC_IN_23") (pintype "bidirectional"))
      (node (ref "R13") (pin "2") (pintype "passive"))
      (node (ref "Y1") (pin "2") (pinfunction "OSC2_2") (pintype "passive"))
    )
    (net (code "31") (name "/OSC_OUT") (class "Default")
      (node (ref "C29") (pin "1") (pinfunction "1_1") (pintype "passive"))
      (node (ref "MCU1") (pin "24") (pinfunction "PH1<>OSC_OUT_24") (pintype "bidirectional"))
      (node (ref "R13") (pin "1") (pintype "passive"))
      (node (ref "Y1") (pin "1") (pinfunction "OSC1_1") (pintype "passive"))
    )
    (net (code "32") (name "/PA0") (class "Default")
      (node (ref "LANYA1") (pin "4") (pinfunction "RXD_4") (pintype "passive"))
      (node (ref "MCU1") (pin "34") (pinfunction "PA0-WKUP/USART2_CTS/UART4_TX/ETH_MII_CRS/TIM2_CH1_ETR/TIM5_CH1/TIM8_ETR<>ADC123_IN0/WKUP_34") (pintype "bidirectional"))
      (node (ref "P1") (pin "5") (pinfunction "5_5") (pintype "passive"))
    )
    (net (code "33") (name "/PA1") (class "Default")
      (node (ref "LANYA1") (pin "3") (pinfunction "TXD_3") (pintype "passive"))
      (node (ref "MCU1") (pin "35") (pinfunction "PA1/USART2_RTS/UART4_RX/ETH_RMII_REF_CLK/ETH_MII_RX_CLK/TIM5_CH2/TIM2_CH2<>ADC123_IN1_35") (pintype "bidirectional"))
      (node (ref "P1") (pin "14") (pinfunction "14_14") (pintype "passive"))
    )
    (net (code "34") (name "/PA2") (class "Default")
      (node (ref "FINGER1") (pin "3") (pinfunction "RXD_3") (pintype "passive"))
      (node (ref "MCU1") (pin "36") (pinfunction "PA2/USART2_TX/TIM5_CH3/TIM9_CH1/TIM2_CH3/ETH_MDIO<>ADC123_IN2_36") (pintype "bidirectional"))
      (node (ref "P1") (pin "6") (pinfunction "6_6") (pintype "passive"))
    )
    (net (code "35") (name "/PA3") (class "Default")
      (node (ref "FINGER1") (pin "4") (pinfunction "TXD_4") (pintype "passive"))
      (node (ref "MCU1") (pin "37") (pinfunction "PA3/USART2_RX/TIM5_CH4/TIM9_CH2/TIM2_CH4/OTG_HS_ULPI_D0/ETH_MII_COL<>ADC123_IN3_37") (pintype "bidirectional"))
      (node (ref "P1") (pin "15") (pinfunction "15_15") (pintype "passive"))
    )
    (net (code "36") (name "/PA4") (class "Default")
      (node (ref "MCU1") (pin "40") (pinfunction "PA4/SPI1_NSS/SPI3_NSS/USART2_CK/DCMI_HSYNC/OTG_HS_SOF/I2S3_WS<>ADC12_IN4/DAC1_OUT_40") (pintype "bidirectional"))
      (node (ref "RFID1") (pin "1") (pinfunction "SDA_1") (pintype "passive"))
    )
    (net (code "37") (name "/PA5") (class "Default")
      (node (ref "MCU1") (pin "41") (pinfunction "PA5/SPI1_SCK/OTG_HS_ULPI_CK/TIM2_CH1_ETR/TIM8_CHIN<>ADC12_IN5/DAC2_OUT_41") (pintype "bidirectional"))
      (node (ref "RFID1") (pin "2") (pinfunction "SCK_2") (pintype "passive"))
    )
    (net (code "38") (name "/PA6") (class "Default")
      (node (ref "MCU1") (pin "42") (pinfunction "PA6/SPI1_MISO/TIM8_BKIN/TIM13_CH1/DCMI_PIXCLK/TIM3_CH1/TIM1_BKIN<>ADC12_IN6_42") (pintype "bidirectional"))
      (node (ref "RFID1") (pin "4") (pinfunction "MISO_4") (pintype "passive"))
    )
    (net (code "39") (name "/PA7") (class "Default")
      (node (ref "MCU1") (pin "43") (pinfunction "PA7/SPI1_MOSI/TIM8_CH1N/TIM14_CH1/TIM3_CH2/ETH_MII_RX_DV/TIM1_CH1N/RMII_CRS_DV<>ADC12_IN7_43") (pintype "bidirectional"))
      (node (ref "RFID1") (pin "3") (pinfunction "MOSI_3") (pintype "passive"))
    )
    (net (code "40") (name "/PA8") (class "Default")
      (node (ref "MCU1") (pin "100") (pinfunction "PA8/MCO1/USART1_CK/TIM1_CH1/I2C3_SCL/OTG_FS_SOF_100") (pintype "bidirectional"))
      (node (ref "R16") (pin "1") (pintype "passive"))
    )
    (net (code "41") (name "/PA9") (class "Default")
      (node (ref "MCU1") (pin "101") (pinfunction "PA9/USART1_TX/TIM1_CH2/I2C3_SMBA/DCMI_D0<>OTG_FS___VBUS_101") (pintype "bidirectional"))
      (node (ref "P1") (pin "8") (pinfunction "8_8") (pintype "passive"))
    )
    (net (code "42") (name "/PA10") (class "Default")
      (node (ref "MCU1") (pin "102") (pinfunction "PA10/USART1_RX/TIM1_CH3/OTG_FS_ID/DCMI_D1_102") (pintype "bidirectional"))
      (node (ref "P1") (pin "17") (pinfunction "17_17") (pintype "passive"))
    )
    (net (code "43") (name "/PA13") (class "Default")
      (node (ref "MCU1") (pin "105") (pinfunction "PA13/JTMS-SWDIO_105") (pintype "bidirectional"))
      (node (ref "R15") (pin "1") (pintype "passive"))
      (node (ref "SWD1") (pin "3") (pinfunction "3_3") (pintype "passive"))
    )
    (net (code "44") (name "/PA14") (class "Default")
      (node (ref "MCU1") (pin "109") (pinfunction "PA14/JTCK-SWCLK_109") (pintype "bidirectional"))
      (node (ref "R14") (pin "1") (pintype "passive"))
      (node (ref "SWD1") (pin "2") (pinfunction "2_2") (pintype "passive"))
    )
    (net (code "45") (name "/PA15") (class "Default")
      (node (ref "JP1") (pin "43") (pinfunction "43_43") (pintype "passive"))
      (node (ref "MCU1") (pin "110") (pinfunction "PA15/JTDI/SPI3_NSS/I2S3_WS/TIM2_CH1_ETR/SPI1_NSS_110") (pintype "bidirectional"))
    )
    (net (code "46") (name "/PB0") (class "Default")
      (node (ref "JP1") (pin "34") (pinfunction "34_34") (pintype "passive"))
      (node (ref "MCU1") (pin "46") (pinfunction "PB0/TIM3_CH3/TIM8_CH2N/OTG_HS_ULPI_D1/ETH_MII_RXD2/TIM1_CH2N<>ADC12_IN8_46") (pintype "bidirectional"))
    )
    (net (code "47") (name "/PB1") (class "Default")
      (node (ref "JP1") (pin "31") (pinfunction "31_31") (pintype "passive"))
      (node (ref "MCU1") (pin "47") (pinfunction "PB1/TIM3_CH4/TIM8_CH3N/OTG_HS_ULPI_D2/ETH_MII_RXD3/OTG_HS_INTN/TIM1_CH3N<>ADC12_IN9_47") (pintype "bidirectional"))
    )
    (net (code "48") (name "/PB3") (class "Default")
      (node (ref "JP1") (pin "35") (pinfunction "35_35") (pintype "passive"))
      (node (ref "MCU1") (pin "133") (pinfunction "PB3/JTDO/_TRACESWO/SPI3_SCK/I2S3_SCK/TIM2_CH2/SPI1_SCK_133") (pintype "bidirectional"))
    )
    (net (code "49") (name "/PB4") (class "Default")
      (node (ref "JP1") (pin "37") (pinfunction "37_37") (pintype "passive"))
      (node (ref "MCU1") (pin "134") (pinfunction "PB4/NJTRST/SPI3_MISO/TIM3_CH1/SPI1_MISO_134") (pintype "bidirectional"))
    )
    (net (code "50") (name "/PB5") (class "Default")
      (node (ref "JP1") (pin "39") (pinfunction "39_39") (pintype "passive"))
      (node (ref "MCU1") (pin "135") (pinfunction "PB5/I2C1_SMBA/CAN2_RX/OTG_HS_ULPI_D7/ETH_PPS_OUT/TIM3_CH2/SPI1_MOSI/SPI3_MOSI/DCMI_D10/I2S3_SD_135") (pintype "bidirectional"))
    )
    (net (code "51") (name "/PB6") (class "Default")
      (node (ref "JP1") (pin "41") (pinfunction "41_41") (pintype "passive"))
      (node (ref "MCU1") (pin "136") (pinfunction "PB6/I2C1_SCL/TIM4_CH1/CAN2_TX/OTG_FS_INTN/DCMI_D5/USART1_TX_136") (pintype "bidirectional"))
    )
    (net (code "52") (name "/PB10") (class "Default")
      (node (ref "JP1") (pin "36") (pinfunction "36_36") (pintype "passive"))
      (node (ref "MCU1") (pin "69") (pinfunction "PB10/SPI2_SCK/I2S2_SCK/I2C2_SCL/USART3_TX/OTG_HS_ULPI_D3/ETH_MII_RX_ER/OTG_HS_SCL/TIM2_CH3_69") (pintype "bidirectional"))
      (node (ref "P1") (pin "7") (pinfunction "7_7") (pintype "passive"))
    )
    (net (code "53") (name "/PB11") (class "Default")
      (node (ref "JP1") (pin "38") (pinfunction "38_38") (pintype "passive"))
      (node (ref "MCU1") (pin "70") (pinfunction "PB11/I2C2_SDA/USART3_RX/OTG_HS_ULPI_D4/ETH_RMII_TX_EN/ETH_MII_TX_EN/OTG_HS_SDA/TIM2_CH_70") (pintype "bidirectional"))
      (node (ref "P1") (pin "16") (pinfunction "16_16") (pintype "passive"))
    )
    (net (code "54") (name "/PB12") (class "Default")
      (node (ref "MCU1") (pin "73") (pinfunction "PB12/SPI2_NSS/I2S2_WS/I2C2_SMBA/USART3_CK/TIM1_BKIN/CAN2_RX/OTG_HS_ULPI_D5/ETH_RMII_TXD0/ETH_MII_TXD0/OTG_HS_ID_73") (pintype "bidirectional"))
      (node (ref "TIME1") (pin "7") (pinfunction "SCLK_7") (pintype "passive"))
    )
    (net (code "55") (name "/PB13") (class "Default")
      (node (ref "MCU1") (pin "74") (pinfunction "PB13/SPI2_SCK/I2S2_SCK/USART3_CTS/TIM1_CH1N/CAN2_TX/OTG_HS_ULPI_D6/ETH_RMII_TXD1/ETH_MII_TXD1<>OTG_HS___VBUS_74") (pintype "bidirectional"))
      (node (ref "TIME1") (pin "6") (pinfunction "I/O_6") (pintype "passive"))
    )
    (net (code "56") (name "/PB14") (class "Default")
      (node (ref "MCU1") (pin "75") (pinfunction "PB14/SPI2_MISO/TIM1_CH2N/TIM12_CH1/OTG_HS_DM/USART3_RTS/TIM8_CH2N_75") (pintype "bidirectional"))
      (node (ref "TIME1") (pin "5") (pinfunction "CE_5") (pintype "passive"))
    )
    (net (code "57") (name "/PC4") (class "Default")
      (node (ref "MCU1") (pin "44") (pinfunction "PC4/ETH_RMII_RX_D0/ETH_MII_RX_D0<>ADC12_IN14_44") (pintype "bidirectional"))
      (node (ref "RFID1") (pin "7") (pinfunction "RST_7") (pintype "passive"))
    )
    (net (code "58") (name "/PC8") (class "Default")
      (node (ref "MCU1") (pin "98") (pinfunction "PC8/TIM8_CH3/SDIO_D0/TIM3_CH3/USART6_CK/DCMI_D2_98") (pintype "bidirectional"))
      (node (ref "R5") (pin "1") (pintype "passive"))
      (node (ref "sdcard1") (pin "7") (pinfunction "DAT0_7") (pintype "passive"))
    )
    (net (code "59") (name "/PC13") (class "Default")
      (node (ref "JP1") (pin "33") (pinfunction "33_33") (pintype "passive"))
      (node (ref "MCU1") (pin "7") (pinfunction "PC13<>RTC_AF1__7__7_7") (pintype "bidirectional"))
    )
    (net (code "60") (name "/PD2") (class "Default")
      (node (ref "MCU1") (pin "116") (pinfunction "PD2/TIM3_ETR/UART5_RX/SDIO_CMD/DCMI_D11_116") (pintype "bidirectional"))
      (node (ref "R3") (pin "1") (pintype "passive"))
      (node (ref "sdcard1") (pin "3") (pinfunction "CMD_3") (pintype "passive"))
    )
    (net (code "61") (name "/PD3") (class "Default")
      (node (ref "MCU1") (pin "117") (pinfunction "PD3/FSMC_CLK/USART2_CTS_117") (pintype "bidirectional"))
      (node (ref "sdcard1") (pin "9") (pinfunction "CK-IN_9") (pintype "passive"))
    )
    (net (code "62") (name "/PF11") (class "Default")
      (node (ref "JP1") (pin "30") (pinfunction "30_30") (pintype "passive"))
      (node (ref "MCU1") (pin "49") (pinfunction "PF11/DCMI_12_49") (pintype "bidirectional"))
    )
    (net (code "63") (name "/PG9") (class "Default")
      (node (ref "A1") (pin "17") (pinfunction "UART1_TX_17") (pintype "passive"))
      (node (ref "MCU1") (pin "124") (pinfunction "PG9/USART6_RX/FSMC_NE2/FSMC_NCE3_124") (pintype "bidirectional"))
      (node (ref "P1") (pin "9") (pinfunction "9_9") (pintype "passive"))
    )
    (net (code "64") (name "/PG14") (class "Default")
      (node (ref "A1") (pin "18") (pinfunction "UART1_RX_18") (pintype "passive"))
      (node (ref "MCU1") (pin "129") (pinfunction "PG14/FSMC_A25/USART6_TX/ETH_MII_TXD1/ETH_RMII_TXD1_129") (pintype "bidirectional"))
      (node (ref "P1") (pin "18") (pinfunction "18_18") (pintype "passive"))
    )
    (net (code "65") (name "/RESET") (class "Default")
      (node (ref "C31") (pin "2") (pintype "passive"))
      (node (ref "JP1") (pin "5") (pinfunction "5_5") (pintype "passive"))
      (node (ref "MCU1") (pin "25") (pinfunction "NRST_25") (pintype "input"))
      (node (ref "R17") (pin "1") (pintype "passive"))
      (node (ref "RST1") (pin "1") (pinfunction "1_1") (pintype "passive"))
    )
    (net (code "66") (name "/SDIO_D1") (class "Default")
      (node (ref "MCU1") (pin "99") (pinfunction "PC9/I2S2_CKIN/I2S3_CKIN/MCO2/TIM8_CH4/SDIO_D1/I2C3_SDA/DCMI_D3/TIM3_CH4_99") (pintype "bidirectional"))
      (node (ref "R6") (pin "1") (pintype "passive"))
      (node (ref "sdcard1") (pin "8") (pinfunction "DAT1_8") (pintype "passive"))
    )
    (net (code "67") (name "/SDIO_D2") (class "Default")
      (node (ref "MCU1") (pin "111") (pinfunction "PC10/SPI3_SCK/I2S3_SCK/UART4_TX/SDIO_D2/DCMI_D8/USART3_TX_111") (pintype "bidirectional"))
      (node (ref "R1") (pin "1") (pintype "passive"))
      (node (ref "sdcard1") (pin "1") (pinfunction "DAT2_1") (pintype "passive"))
    )
    (net (code "68") (name "/SDIO_D3") (class "Default")
      (node (ref "R2") (pin "1") (pintype "passive"))
      (node (ref "sdcard1") (pin "2") (pinfunction "CD/DAT3_2") (pintype "passive"))
    )
    (net (code "69") (name "/SDIO_SCK") (class "Default")
      (node (ref "MCU1") (pin "113") (pinfunction "PC12/UART5_TX/SDIO_CK/DCMI_D9/SPI3_MOSI/I2S3_SD/USART3_CK_113") (pintype "bidirectional"))
      (node (ref "R4") (pin "1") (pintype "passive"))
      (node (ref "sdcard1") (pin "5") (pinfunction "CLK_5") (pintype "passive"))
    )
    (net (code "70") (name "/VBAT") (class "Default")
      (node (ref "C30") (pin "2") (pintype "passive"))
      (node (ref "D3") (pin "2") (pinfunction "K_2") (pintype "passive"))
      (node (ref "D4") (pin "2") (pinfunction "K_2") (pintype "passive"))
      (node (ref "MCU1") (pin "6") (pinfunction "VBAT_6") (pintype "power_in"))
      (node (ref "TIME1") (pin "8") (pinfunction "VCC1_8") (pintype "passive"))
    )
    (net (code "71") (name "GND") (class "Default")
      (node (ref "A1") (pin "30") (pinfunction "GND_30") (pintype "passive"))
      (node (ref "BAT1") (pin "2") (pinfunction "GND_2") (pintype "passive"))
      (node (ref "C1") (pin "1") (pintype "passive"))
      (node (ref "C10") (pin "1") (pintype "passive"))
      (node (ref "C11") (pin "2") (pintype "passive"))
      (node (ref "C12") (pin "2") (pintype "passive"))
      (node (ref "C13") (pin "2") (pintype "passive"))
      (node (ref "C14") (pin "1") (pintype "passive"))
      (node (ref "C15") (pin "2") (pinfunction "2_2") (pintype "passive"))
      (node (ref "C16") (pin "1") (pinfunction "1_1") (pintype "passive"))
      (node (ref "C17") (pin "1") (pinfunction "1_1") (pintype "passive"))
      (node (ref "C18") (pin "1") (pinfunction "1_1") (pintype "passive"))
      (node (ref "C19") (pin "1") (pinfunction "1_1") (pintype "passive"))
      (node (ref "C2") (pin "2") (pinfunction "GND_2") (pintype "passive"))
      (node (ref "C20") (pin "1") (pinfunction "1_1") (pintype "passive"))
      (node (ref "C21") (pin "1") (pinfunction "1_1") (pintype "passive"))
      (node (ref "C22") (pin "1") (pinfunction "1_1") (pintype "passive"))
      (node (ref "C23") (pin "1") (pinfunction "1_1") (pintype "passive"))
      (node (ref "C24") (pin "1") (pinfunction "1_1") (pintype "passive"))
      (node (ref "C25") (pin "1") (pinfunction "1_1") (pintype "passive"))
      (node (ref "C26") (pin "1") (pinfunction "1_1") (pintype "passive"))
      (node (ref "C27") (pin "1") (pinfunction "1_1") (pintype "passive"))
      (node (ref "C28") (pin "1") (pinfunction "1_1") (pintype "passive"))
      (node (ref "C29") (pin "2") (pinfunction "2_2") (pintype "passive"))
      (node (ref "C3") (pin "1") (pintype "passive"))
      (node (ref "C30") (pin "1") (pintype "passive"))
      (node (ref "C31") (pin "1") (pintype "passive"))
      (node (ref "C4") (pin "2") (pinfunction "GND_2") (pintype "passive"))
      (node (ref "C5") (pin "1") (pintype "passive"))
      (node (ref "C6") (pin "1") (pintype "passive"))
      (node (ref "C7") (pin "2") (pintype "passive"))
      (node (ref "C8") (pin "2") (pintype "passive"))
      (node (ref "C9") (pin "1") (pintype "passive"))
      (node (ref "CON1") (pin "2") (pintype "power_in"))
      (node (ref "CON1") (pin "3") (pintype "power_in"))
      (node (ref "D1") (pin "1") (pinfunction "A_1") (pintype "passive"))
      (node (ref "DOOR1") (pin "2") (pinfunction "2_2") (pintype "passive"))
      (node (ref "DOOR1") (pin "3") (pinfunction "3_3") (pintype "passive"))
      (node (ref "FINGER1") (pin "5") (pinfunction "GND_5") (pintype "passive"))
      (node (ref "JP1") (pin "22") (pinfunction "22_22") (pintype "passive"))
      (node (ref "JP1") (pin "26") (pinfunction "26_26") (pintype "passive"))
      (node (ref "JP1") (pin "27") (pinfunction "27_27") (pintype "passive"))
      (node (ref "K1") (pin "1") (pinfunction "1_1") (pintype "passive"))
      (node (ref "K2") (pin "1") (pinfunction "1_1") (pintype "passive"))
      (node (ref "LANYA1") (pin "2") (pinfunction "GND_2") (pintype "passive"))
      (node (ref "MCU1") (pin "107") (pinfunction "VSS_2_107") (pintype "power_in"))
      (node (ref "MCU1") (pin "120") (pinfunction "VSS_10_120") (pintype "power_in"))
      (node (ref "MCU1") (pin "130") (pinfunction "VSS_11_130") (pintype "power_in"))
      (node (ref "MCU1") (pin "16") (pinfunction "VSS_5_16") (pintype "power_in"))
      (node (ref "MCU1") (pin "31") (pinfunction "VSSA_31") (pintype "power_in"))
      (node (ref "MCU1") (pin "32") (pinfunction "VREF+_32") (pintype "power_in"))
      (node (ref "MCU1") (pin "38") (pinfunction "VSS_4_38") (pintype "power_in"))
      (node (ref "MCU1") (pin "51") (pinfunction "VSS_6_51") (pintype "power_in"))
      (node (ref "MCU1") (pin "61") (pinfunction "VSS_7_61") (pintype "power_in"))
      (node (ref "MCU1") (pin "83") (pinfunction "VSS_8_83") (pintype "power_in"))
      (node (ref "MCU1") (pin "94") (pinfunction "VSS_9_94") (pintype "power_in"))
      (node (ref "P1") (pin "12") (pinfunction "12_12") (pintype "passive"))
      (node (ref "P1") (pin "3") (pinfunction "3_3") (pintype "passive"))
      (node (ref "Q1") (pin "2") (pinfunction "E_2") (pintype "passive"))
      (node (ref "Q2") (pin "2") (pinfunction "E_2") (pintype "passive"))
      (node (ref "R10") (pin "1") (pinfunction "1_1") (pintype "passive"))
      (node (ref "R7") (pin "1") (pintype "passive"))
      (node (ref "R8") (pin "1") (pintype "passive"))
      (node (ref "RFID1") (pin "6") (pinfunction "GND_6") (pintype "passive"))
      (node (ref "RST1") (pin "2") (pinfunction "2_2") (pintype "passive"))
      (node (ref "SWD1") (pin "1") (pinfunction "1_1") (pintype "passive"))
      (node (ref "TIME1") (pin "4") (pinfunction "GND_4") (pintype "passive"))
      (node (ref "U1") (pin "3") (pinfunction "GND_3") (pintype "passive"))
      (node (ref "U1") (pin "5") (pinfunction "ON/OFF_5") (pintype "passive"))
      (node (ref "U2") (pin "1") (pinfunction "GND_1") (pintype "passive"))
      (node (ref "sdcard1") (pin "6") (pinfunction "VSS_6") (pintype "passive"))
    )
    (net (code "72") (name "Net-(A1-PWR)") (class "Default")
      (node (ref "A1") (pin "27") (pinfunction "PWR_27") (pintype "passive"))
      (node (ref "R7") (pin "2") (pintype "passive"))
    )
    (net (code "73") (name "Net-(BAT1-VCC)") (class "Default")
      (node (ref "BAT1") (pin "1") (pinfunction "VCC_1") (pintype "passive"))
      (node (ref "D4") (pin "1") (pinfunction "A_1") (pintype "passive"))
    )
    (net (code "74") (name "Net-(BEEP1-G)") (class "Default")
      (node (ref "BEEP1") (pin "2") (pinfunction "G_2") (pintype "passive"))
      (node (ref "Q1") (pin "3") (pinfunction "C_3") (pintype "passive"))
    )
    (net (code "75") (name "Net-(CON1-Pad1)") (class "Default")
      (node (ref "CON1") (pin "1") (pintype "power_in"))
      (node (ref "FU1") (pin "1") (pinfunction "1_1") (pintype "passive"))
    )
    (net (code "76") (name "Net-(D1-K)") (class "Default")
      (node (ref "D1") (pin "2") (pinfunction "K_2") (pintype "passive"))
      (node (ref "L1") (pin "1") (pinfunction "1_1") (pintype "passive"))
      (node (ref "U1") (pin "2") (pinfunction "OUT_2") (pintype "passive"))
    )
    (net (code "77") (name "Net-(D2-A)") (class "Default")
      (node (ref "D2") (pin "1") (pinfunction "A_1") (pintype "passive"))
      (node (ref "FU1") (pin "2") (pinfunction "2_2") (pintype "passive"))
    )
    (net (code "78") (name "Net-(D2-K)") (class "Default")
      (node (ref "D2") (pin "2") (pinfunction "K_2") (pintype "passive"))
      (node (ref "S1") (pin "1") (pinfunction "I/O1_1") (pintype "passive"))
    )
    (net (code "79") (name "Net-(D5-A)") (class "Default")
      (node (ref "D5") (pin "1") (pinfunction "A_1") (pintype "passive"))
      (node (ref "JK1") (pin "2") (pinfunction "2_2") (pintype "passive"))
      (node (ref "Q2") (pin "3") (pinfunction "C_3") (pintype "passive"))
    )
    (net (code "80") (name "Net-(DOOR1-Pad4)") (class "Default")
      (node (ref "DOOR1") (pin "4") (pinfunction "4_4") (pintype "passive"))
      (node (ref "JK1") (pin "3") (pinfunction "3_3") (pintype "passive"))
    )
    (net (code "81") (name "Net-(DS1-A)") (class "Default")
      (node (ref "DS1") (pin "1") (pinfunction "A_1") (pintype "passive"))
      (node (ref "R18") (pin "2") (pintype "passive"))
    )
    (net (code "82") (name "Net-(DS2-A)") (class "Default")
      (node (ref "DS2") (pin "1") (pinfunction "A_1") (pintype "passive"))
      (node (ref "R19") (pin "2") (pintype "passive"))
    )
    (net (code "83") (name "Net-(DS3-A)") (class "Default")
      (node (ref "DS3") (pin "1") (pinfunction "A_1") (pintype "passive"))
      (node (ref "R20") (pin "2") (pintype "passive"))
    )
    (net (code "84") (name "Net-(LED1-K)") (class "Default")
      (node (ref "LED1") (pin "2") (pinfunction "K_2") (pintype "passive"))
      (node (ref "R8") (pin "2") (pintype "passive"))
    )
    (net (code "85") (name "Net-(MCU1-PF8{slash}TIM13_CH1{slash}FSMC_NIOWR<>ADC3_IN6)") (class "Default")
      (node (ref "MCU1") (pin "20") (pinfunction "PF8/TIM13_CH1/FSMC_NIOWR<>ADC3_IN6_20") (pintype "bidirectional"))
      (node (ref "R9") (pin "1") (pinfunction "1_1") (pintype "passive"))
    )
    (net (code "86") (name "Net-(MCU1-VCAP_1)") (class "Default")
      (node (ref "C11") (pin "1") (pintype "passive"))
      (node (ref "MCU1") (pin "71") (pinfunction "VCAP_1_71") (pintype "power_in"))
    )
    (net (code "87") (name "Net-(MCU1-VCAP_2)") (class "Default")
      (node (ref "C12") (pin "1") (pintype "passive"))
      (node (ref "MCU1") (pin "106") (pinfunction "VCAP_2_106") (pintype "power_in"))
    )
    (net (code "88") (name "Net-(P1-Pad2)") (class "Default")
      (node (ref "P1") (pin "2") (pinfunction "2_2") (pintype "passive"))
      (node (ref "R11") (pin "2") (pintype "passive"))
    )
    (net (code "89") (name "Net-(P1-Pad11)") (class "Default")
      (node (ref "P1") (pin "11") (pinfunction "11_11") (pintype "passive"))
      (node (ref "R12") (pin "1") (pintype "passive"))
    )
    (net (code "90") (name "Net-(Q1-B)") (class "Default")
      (node (ref "Q1") (pin "1") (pinfunction "B_1") (pintype "passive"))
      (node (ref "R10") (pin "2") (pinfunction "2_2") (pintype "passive"))
      (node (ref "R9") (pin "2") (pinfunction "2_2") (pintype "passive"))
    )
    (net (code "91") (name "Net-(Q2-B)") (class "Default")
      (node (ref "Q2") (pin "1") (pinfunction "B_1") (pintype "passive"))
      (node (ref "R16") (pin "2") (pintype "passive"))
    )
    (net (code "92") (name "Net-(TIME1-X1)") (class "Default")
      (node (ref "TIME1") (pin "2") (pinfunction "X1_2") (pintype "passive"))
      (node (ref "Y2") (pin "1") (pinfunction "OSC1_1") (pintype "passive"))
    )
    (net (code "93") (name "Net-(TIME1-X2)") (class "Default")
      (node (ref "TIME1") (pin "3") (pinfunction "X2_3") (pintype "passive"))
      (node (ref "Y2") (pin "2") (pinfunction "OSC2_2") (pintype "passive"))
    )
    (net (code "94") (name "VCC3.3") (class "Default")
      (node (ref "BEEP1") (pin "1") (pinfunction "P_1") (pintype "passive"))
      (node (ref "C1") (pin "2") (pintype "passive"))
      (node (ref "C10") (pin "2") (pintype "passive"))
      (node (ref "C13") (pin "1") (pintype "passive"))
      (node (ref "C16") (pin "2") (pinfunction "2_2") (pintype "passive"))
      (node (ref "C17") (pin "2") (pinfunction "2_2") (pintype "passive"))
      (node (ref "C18") (pin "2") (pinfunction "2_2") (pintype "passive"))
      (node (ref "C19") (pin "2") (pinfunction "2_2") (pintype "passive"))
      (node (ref "C20") (pin "2") (pinfunction "2_2") (pintype "passive"))
      (node (ref "C21") (pin "2") (pinfunction "2_2") (pintype "passive"))
      (node (ref "C22") (pin "2") (pinfunction "2_2") (pintype "passive"))
      (node (ref "C23") (pin "2") (pinfunction "2_2") (pintype "passive"))
      (node (ref "C24") (pin "2") (pinfunction "2_2") (pintype "passive"))
      (node (ref "C25") (pin "2") (pinfunction "2_2") (pintype "passive"))
      (node (ref "C26") (pin "2") (pinfunction "2_2") (pintype "passive"))
      (node (ref "C27") (pin "2") (pinfunction "2_2") (pintype "passive"))
      (node (ref "C28") (pin "2") (pinfunction "2_2") (pintype "passive"))
      (node (ref "C9") (pin "2") (pintype "passive"))
      (node (ref "D3") (pin "1") (pinfunction "A_1") (pintype "passive"))
      (node (ref "JP1") (pin "24") (pinfunction "24_24") (pintype "passive"))
      (node (ref "JP1") (pin "25") (pinfunction "25_25") (pintype "passive"))
      (node (ref "LANYA1") (pin "1") (pinfunction "VCC_1") (pintype "passive"))
      (node (ref "MCU1") (pin "108") (pinfunction "VDD_2_108") (pintype "power_in"))
      (node (ref "MCU1") (pin "121") (pinfunction "VDD_10_121") (pintype "power_in"))
      (node (ref "MCU1") (pin "131") (pinfunction "VDD_11_131") (pintype "power_in"))
      (node (ref "MCU1") (pin "144") (pinfunction "VDD_3_144") (pintype "power_in"))
      (node (ref "MCU1") (pin "17") (pinfunction "VDD_5_17") (pintype "power_in"))
      (node (ref "MCU1") (pin "30") (pinfunction "VDD_12_30") (pintype "power_in"))
      (node (ref "MCU1") (pin "33") (pinfunction "VDDA_33") (pintype "power_in"))
      (node (ref "MCU1") (pin "39") (pinfunction "VDD_4_39") (pintype "power_in"))
      (node (ref "MCU1") (pin "52") (pinfunction "VDD_6_52") (pintype "power_in"))
      (node (ref "MCU1") (pin "62") (pinfunction "VDD_7_62") (pintype "power_in"))
      (node (ref "MCU1") (pin "72") (pinfunction "VDD_1_72") (pintype "power_in"))
      (node (ref "MCU1") (pin "84") (pinfunction "VDD_8_84") (pintype "power_in"))
      (node (ref "MCU1") (pin "95") (pinfunction "VDD_9_95") (pintype "power_in"))
      (node (ref "P1") (pin "1") (pinfunction "1_1") (pintype "passive"))
      (node (ref "P1") (pin "10") (pinfunction "10_10") (pintype "passive"))
      (node (ref "R1") (pin "2") (pintype "passive"))
      (node (ref "R14") (pin "2") (pintype "passive"))
      (node (ref "R15") (pin "2") (pintype "passive"))
      (node (ref "R17") (pin "2") (pintype "passive"))
      (node (ref "R18") (pin "1") (pintype "passive"))
      (node (ref "R19") (pin "1") (pintype "passive"))
      (node (ref "R2") (pin "2") (pintype "passive"))
      (node (ref "R20") (pin "1") (pintype "passive"))
      (node (ref "R3") (pin "2") (pintype "passive"))
      (node (ref "R4") (pin "2") (pintype "passive"))
      (node (ref "R5") (pin "2") (pintype "passive"))
      (node (ref "R6") (pin "2") (pintype "passive"))
      (node (ref "RFID1") (pin "8") (pinfunction "3.3V_8") (pintype "passive"))
      (node (ref "TIME1") (pin "1") (pinfunction "VCC2_1") (pintype "passive"))
      (node (ref "U2") (pin "2") (pinfunction "OUT_2") (pintype "passive"))
      (node (ref "sdcard1") (pin "4") (pinfunction "VDD_4") (pintype "passive"))
    )
    (net (code "95") (name "VCC5") (class "Default")
      (node (ref "A1") (pin "29") (pinfunction "VUSB_29") (pintype "passive"))
      (node (ref "C14") (pin "2") (pintype "passive"))
      (node (ref "C4") (pin "1") (pinfunction "VCC_1") (pintype "passive"))
      (node (ref "C5") (pin "2") (pintype "passive"))
      (node (ref "C6") (pin "2") (pintype "passive"))
      (node (ref "C7") (pin "1") (pintype "passive"))
      (node (ref "C8") (pin "1") (pintype "passive"))
      (node (ref "FINGER1") (pin "6") (pinfunction "VCC_6") (pintype "passive"))
      (node (ref "JP1") (pin "28") (pinfunction "28_28") (pintype "passive"))
      (node (ref "L1") (pin "2") (pinfunction "2_2") (pintype "passive"))
      (node (ref "LED1") (pin "1") (pinfunction "A_1") (pintype "passive"))
      (node (ref "P1") (pin "13") (pinfunction "13_13") (pintype "passive"))
      (node (ref "P1") (pin "4") (pinfunction "4_4") (pintype "passive"))
      (node (ref "U1") (pin "4") (pinfunction "FB_4") (pintype "passive"))
      (node (ref "U2") (pin "3") (pinfunction "IN_3") (pintype "passive"))
    )
    (net (code "96") (name "VCC12") (class "Default")
      (node (ref "C2") (pin "1") (pinfunction "VCC_1") (pintype "passive"))
      (node (ref "C3") (pin "2") (pintype "passive"))
      (node (ref "D5") (pin "2") (pinfunction "K_2") (pintype "passive"))
      (node (ref "DOOR1") (pin "1") (pinfunction "1_1") (pintype "passive"))
      (node (ref "JK1") (pin "1") (pinfunction "1_1") (pintype "passive"))
      (node (ref "JK1") (pin "4") (pinfunction "4_4") (pintype "passive"))
      (node (ref "S1") (pin "2") (pinfunction "TAP1_2") (pintype "passive"))
      (node (ref "U1") (pin "1") (pinfunction "VIN_1") (pintype "passive"))
    )
    (net (code "97") (name "unconnected-(A1-ADC0-Pad13)") (class "Default")
      (node (ref "A1") (pin "13") (pinfunction "ADC0_13") (pintype "passive"))
    )
    (net (code "98") (name "unconnected-(A1-ADC1-Pad12)") (class "Default")
      (node (ref "A1") (pin "12") (pinfunction "ADC1_12") (pintype "passive"))
    )
    (net (code "99") (name "unconnected-(A1-GND-Pad16)") (class "Default")
      (node (ref "A1") (pin "16") (pinfunction "GND_16") (pintype "passive"))
    )
    (net (code "100") (name "unconnected-(A1-GPS_RX-Pad21)") (class "Default")
      (node (ref "A1") (pin "21") (pinfunction "GPS_RX_21") (pintype "passive"))
    )
    (net (code "101") (name "unconnected-(A1-GPS_TX-Pad22)") (class "Default")
      (node (ref "A1") (pin "22") (pinfunction "GPS_TX_22") (pintype "passive"))
    )
    (net (code "102") (name "unconnected-(A1-HST_RX-Pad26)") (class "Default")
      (node (ref "A1") (pin "26") (pinfunction "HST_RX_26") (pintype "passive"))
    )
    (net (code "103") (name "unconnected-(A1-HST_TX-Pad25)") (class "Default")
      (node (ref "A1") (pin "25") (pinfunction "HST_TX_25") (pintype "passive"))
    )
    (net (code "104") (name "unconnected-(A1-I2C2_SCL-Pad10)") (class "Default")
      (node (ref "A1") (pin "10") (pinfunction "I2C2_SCL_10") (pintype "passive"))
    )
    (net (code "105") (name "unconnected-(A1-I2C2_SDA-Pad11)") (class "Default")
      (node (ref "A1") (pin "11") (pinfunction "I2C2_SDA_11") (pintype "passive"))
    )
    (net (code "106") (name "unconnected-(A1-IO2-Pad19)") (class "Default")
      (node (ref "A1") (pin "19") (pinfunction "IO2_19") (pintype "passive"))
    )
    (net (code "107") (name "unconnected-(A1-IO3-Pad20)") (class "Default")
      (node (ref "A1") (pin "20") (pinfunction "IO3_20") (pintype "passive"))
    )
    (net (code "108") (name "unconnected-(A1-IO6-Pad23)") (class "Default")
      (node (ref "A1") (pin "23") (pinfunction "IO6_23") (pintype "passive"))
    )
    (net (code "109") (name "unconnected-(A1-IO7-Pad24)") (class "Default")
      (node (ref "A1") (pin "24") (pinfunction "IO7_24") (pintype "passive"))
    )
    (net (code "110") (name "unconnected-(A1-IO25-Pad1)") (class "Default")
      (node (ref "A1") (pin "1") (pinfunction "IO25_1") (pintype "passive"))
    )
    (net (code "111") (name "unconnected-(A1-IO29-Pad4)") (class "Default")
      (node (ref "A1") (pin "4") (pinfunction "IO29_4") (pintype "passive"))
    )
    (net (code "112") (name "unconnected-(A1-IO30-Pad2)") (class "Default")
      (node (ref "A1") (pin "2") (pinfunction "IO30_2") (pintype "passive"))
    )
    (net (code "113") (name "unconnected-(A1-IO326-Pad3)") (class "Default")
      (node (ref "A1") (pin "3") (pinfunction "IO326_3") (pintype "passive"))
    )
    (net (code "114") (name "unconnected-(A1-LCD_CS-Pad9)") (class "Default")
      (node (ref "A1") (pin "9") (pinfunction "LCD_CS_9") (pintype "passive"))
    )
    (net (code "115") (name "unconnected-(A1-LCD_DC-Pad6)") (class "Default")
      (node (ref "A1") (pin "6") (pinfunction "LCD_DC_6") (pintype "passive"))
    )
    (net (code "116") (name "unconnected-(A1-LCD_DIO-Pad7)") (class "Default")
      (node (ref "A1") (pin "7") (pinfunction "LCD_DIO_7") (pintype "passive"))
    )
    (net (code "117") (name "unconnected-(A1-LCD_RST-Pad8)") (class "Default")
      (node (ref "A1") (pin "8") (pinfunction "LCD_RST_8") (pintype "passive"))
    )
    (net (code "118") (name "unconnected-(A1-LCD_SCK-Pad5)") (class "Default")
      (node (ref "A1") (pin "5") (pinfunction "LCD_SCK_5") (pintype "passive"))
    )
    (net (code "119") (name "unconnected-(A1-RESET-Pad28)") (class "Default")
      (node (ref "A1") (pin "28") (pinfunction "RESET_28") (pintype "passive"))
    )
    (net (code "120") (name "unconnected-(A1-VBAT-Pad15)") (class "Default")
      (node (ref "A1") (pin "15") (pinfunction "VBAT_15") (pintype "passive"))
    )
    (net (code "121") (name "unconnected-(A1-VIO-Pad14)") (class "Default")
      (node (ref "A1") (pin "14") (pinfunction "VIO_14") (pintype "passive"))
    )
    (net (code "122") (name "unconnected-(FINGER1-BL-Pad2)") (class "Default")
      (node (ref "FINGER1") (pin "2") (pinfunction "BL_2") (pintype "passive"))
    )
    (net (code "123") (name "unconnected-(FINGER1-RST-Pad1)") (class "Default")
      (node (ref "FINGER1") (pin "1") (pinfunction "RST_1") (pintype "passive"))
    )
    (net (code "124") (name "unconnected-(JP1-Pad32)") (class "Default")
      (node (ref "JP1") (pin "32") (pinfunction "32_32") (pintype "passive+no_connect"))
    )
    (net (code "125") (name "unconnected-(JP1-Pad40)") (class "Default")
      (node (ref "JP1") (pin "40") (pinfunction "40_40") (pintype "passive+no_connect"))
    )
    (net (code "126") (name "unconnected-(JP1-Pad42)") (class "Default")
      (node (ref "JP1") (pin "42") (pinfunction "42_42") (pintype "passive+no_connect"))
    )
    (net (code "127") (name "unconnected-(JP1-Pad44)") (class "Default")
      (node (ref "JP1") (pin "44") (pinfunction "44_44") (pintype "passive+no_connect"))
    )
    (net (code "128") (name "unconnected-(JP1-Pad45)") (class "Default")
      (node (ref "JP1") (pin "45") (pinfunction "45_45") (pintype "passive+no_connect"))
    )
    (net (code "129") (name "unconnected-(JP1-Pad46)") (class "Default")
      (node (ref "JP1") (pin "46") (pinfunction "46_46") (pintype "passive+no_connect"))
    )
    (net (code "130") (name "unconnected-(JP1-Pad47)") (class "Default")
      (node (ref "JP1") (pin "47") (pinfunction "47_47") (pintype "passive+no_connect"))
    )
    (net (code "131") (name "unconnected-(JP1-Pad48)") (class "Default")
      (node (ref "JP1") (pin "48") (pinfunction "48_48") (pintype "passive+no_connect"))
    )
    (net (code "132") (name "unconnected-(JP1-Pad49)") (class "Default")
      (node (ref "JP1") (pin "49") (pinfunction "49_49") (pintype "passive+no_connect"))
    )
    (net (code "133") (name "unconnected-(JP1-Pad50)") (class "Default")
      (node (ref "JP1") (pin "50") (pinfunction "50_50") (pintype "passive+no_connect"))
    )
    (net (code "134") (name "unconnected-(LANYA1-KEY-Pad5)") (class "Default")
      (node (ref "LANYA1") (pin "5") (pinfunction "KEY_5") (pintype "passive+no_connect"))
    )
    (net (code "135") (name "unconnected-(LANYA1-LED-Pad6)") (class "Default")
      (node (ref "LANYA1") (pin "6") (pinfunction "LED_6") (pintype "passive+no_connect"))
    )
    (net (code "136") (name "unconnected-(MCU1-NC{slash}PDR_ON-Pad143)") (class "Default")
      (node (ref "MCU1") (pin "143") (pinfunction "NC/PDR_ON_143") (pintype "power_in"))
    )
    (net (code "137") (name "unconnected-(MCU1-PA11{slash}USART1_CTS{slash}CAN1_RX{slash}TIM1_CH4{slash}OTG_FS_DM-Pad103)") (class "Default")
      (node (ref "MCU1") (pin "103") (pinfunction "PA11/USART1_CTS/CAN1_RX/TIM1_CH4/OTG_FS_DM_103") (pintype "bidirectional"))
    )
    (net (code "138") (name "unconnected-(MCU1-PA12{slash}USART1_RTS{slash}CAN1_TX{slash}TIM1_ETR{slash}OTG_FS_DP-Pad104)") (class "Default")
      (node (ref "MCU1") (pin "104") (pinfunction "PA12/USART1_RTS/CAN1_TX/TIM1_ETR/OTG_FS_DP_104") (pintype "bidirectional"))
    )
    (net (code "139") (name "unconnected-(MCU1-PB7{slash}I2C1_SDA{slash}FSMC_NL{slash}DCMI_VSYNC{slash}USART1_RX{slash}TIM4_CH2-Pad137)") (class "Default")
      (node (ref "MCU1") (pin "137") (pinfunction "PB7/I2C1_SDA/FSMC_NL/DCMI_VSYNC/USART1_RX/TIM4_CH2_137") (pintype "bidirectional"))
    )
    (net (code "140") (name "unconnected-(MCU1-PB8{slash}TIM4_CH3{slash}SDIO_D4{slash}TIM10_CH1{slash}DCMI_D6{slash}OTG_FS_SCL{slash}ETH_MII_TXD3{slash}I2C1_SCL{slash}CAN1_RX-Pad139)") (class "Default")
      (node (ref "MCU1") (pin "139") (pinfunction "PB8/TIM4_CH3/SDIO_D4/TIM10_CH1/DCMI_D6/OTG_FS_SCL/ETH_MII_TXD3/I2C1_SCL/CAN1_RX_139") (pintype "bidirectional"))
    )
    (net (code "141") (name "unconnected-(MCU1-PB9{slash}SPI2_NSS{slash}I2S2_WS{slash}TIM4_CH4{slash}TIM11_CH1{slash}OTG_FS_SDA{slash}SDIO_D5{slash}DCMI_D7{slash}I2C1_SDA{slash}CAN1_TX-Pad140)") (class "Default")
      (node (ref "MCU1") (pin "140") (pinfunction "PB9/SPI2_NSS/I2S2_WS/TIM4_CH4/TIM11_CH1/OTG_FS_SDA/SDIO_D5/DCMI_D7/I2C1_SDA/CAN1_TX_140") (pintype "bidirectional"))
    )
    (net (code "142") (name "unconnected-(MCU1-PC0{slash}OTG_HS_ULPI_STP<>ADC123___IN10-Pad26)") (class "Default")
      (node (ref "MCU1") (pin "26") (pinfunction "PC0/OTG_HS_ULPI_STP<>ADC123___IN10_26") (pintype "bidirectional"))
    )
    (net (code "143") (name "unconnected-(MCU1-PC1{slash}ETH_MDC<>ADC123___IN11-Pad27)") (class "Default")
      (node (ref "MCU1") (pin "27") (pinfunction "PC1/ETH_MDC<>ADC123___IN11_27") (pintype "bidirectional"))
    )
    (net (code "144") (name "unconnected-(MCU1-PC2{slash}SPI2_MISO{slash}OTG_HS_ULPI_DIR{slash}ETH_MII_TXD2<>ADC123___IN12-Pad28)") (class "Default")
      (node (ref "MCU1") (pin "28") (pinfunction "PC2/SPI2_MISO/OTG_HS_ULPI_DIR/ETH_MII_TXD2<>ADC123___IN12_28") (pintype "bidirectional"))
    )
    (net (code "145") (name "unconnected-(MCU1-PC3{slash}SPI2_MOSI{slash}I2S2_SD{slash}OTG_HS_ULPI_NXT{slash}ETH_MII_TX_CLK<>ADC123___IN13-Pad29)") (class "Default")
      (node (ref "MCU1") (pin "29") (pinfunction "PC3/SPI2_MOSI/I2S2_SD/OTG_HS_ULPI_NXT/ETH_MII_TX_CLK<>ADC123___IN13_29") (pintype "bidirectional"))
    )
    (net (code "146") (name "unconnected-(MCU1-PC5{slash}ETH_RMII_RX_D1{slash}ETH_MII_RX_D1<>ADC12_IN15-Pad45)") (class "Default")
      (node (ref "MCU1") (pin "45") (pinfunction "PC5/ETH_RMII_RX_D1/ETH_MII_RX_D1<>ADC12_IN15_45") (pintype "bidirectional"))
    )
    (net (code "147") (name "unconnected-(MCU1-PC6{slash}SPI2_MCK{slash}TIM8_CH1{slash}SDIO_D6{slash}USART6_TX{slash}DCMI_D0{slash}TIM3_CH1-Pad96)") (class "Default")
      (node (ref "MCU1") (pin "96") (pinfunction "PC6/SPI2_MCK/TIM8_CH1/SDIO_D6/USART6_TX/DCMI_D0/TIM3_CH1_96") (pintype "bidirectional"))
    )
    (net (code "148") (name "unconnected-(MCU1-PC7{slash}SPI3_MCK{slash}TIM8_CH2{slash}SDIO_D7{slash}USART6_RX{slash}DCMI_D1{slash}TIM3_CH2-Pad97)") (class "Default")
      (node (ref "MCU1") (pin "97") (pinfunction "PC7/SPI3_MCK/TIM8_CH2/SDIO_D7/USART6_RX/DCMI_D1/TIM3_CH2_97") (pintype "bidirectional"))
    )
    (net (code "149") (name "unconnected-(MCU1-PC11{slash}UART4_RX{slash}_SPI3_MISO{slash}SDIO_D3{slash}DCMI_D4{slash}USART3_RX-Pad112)") (class "Default")
      (node (ref "MCU1") (pin "112") (pinfunction "PC11/UART4_RX/_SPI3_MISO/SDIO_D3/DCMI_D4/USART3_RX_112") (pintype "bidirectional"))
    )
    (net (code "150") (name "unconnected-(MCU1-PC14<>OSC32_IN-Pad8)") (class "Default")
      (node (ref "MCU1") (pin "8") (pinfunction "PC14<>OSC32_IN_8") (pintype "bidirectional"))
    )
    (net (code "151") (name "unconnected-(MCU1-PC15<>OSC32_OUT-Pad9)") (class "Default")
      (node (ref "MCU1") (pin "9") (pinfunction "PC15<>OSC32_OUT_9") (pintype "bidirectional"))
    )
    (net (code "152") (name "unconnected-(MCU1-PD6{slash}FSMC_NWAIT{slash}USART2_RX-Pad122)") (class "Default")
      (node (ref "MCU1") (pin "122") (pinfunction "PD6/FSMC_NWAIT/USART2_RX_122") (pintype "bidirectional"))
    )
    (net (code "153") (name "unconnected-(MCU1-PD7{slash}USART2_CK{slash}FSMC_NE1{slash}FSMC_NCE2-Pad123)") (class "Default")
      (node (ref "MCU1") (pin "123") (pinfunction "PD7/USART2_CK/FSMC_NE1/FSMC_NCE2_123") (pintype "bidirectional"))
    )
    (net (code "154") (name "unconnected-(MCU1-PD11{slash}FSMC_A16{slash}USART3_CTS-Pad80)") (class "Default")
      (node (ref "MCU1") (pin "80") (pinfunction "PD11/FSMC_A16/USART3_CTS_80") (pintype "bidirectional"))
    )
    (net (code "155") (name "unconnected-(MCU1-PD12{slash}FSMC_A17{slash}TIM4_CH1{slash}USART3_RTS-Pad81)") (class "Default")
      (node (ref "MCU1") (pin "81") (pinfunction "PD12/FSMC_A17/TIM4_CH1/USART3_RTS_81") (pintype "bidirectional"))
    )
    (net (code "156") (name "unconnected-(MCU1-PD13{slash}FSMC_A18{slash}TIM4_CH2-Pad82)") (class "Default")
      (node (ref "MCU1") (pin "82") (pinfunction "PD13/FSMC_A18/TIM4_CH2_82") (pintype "bidirectional"))
    )
    (net (code "157") (name "unconnected-(MCU1-PE0{slash}TIM4_ETR{slash}FSMC_NBL0{slash}DCMI_D2-Pad141)") (class "Default")
      (node (ref "MCU1") (pin "141") (pinfunction "PE0/TIM4_ETR/FSMC_NBL0/DCMI_D2_141") (pintype "bidirectional"))
    )
    (net (code "158") (name "unconnected-(MCU1-PE1{slash}FSMC_NBL1{slash}DCMI_D3-Pad142)") (class "Default")
      (node (ref "MCU1") (pin "142") (pinfunction "PE1/FSMC_NBL1/DCMI_D3_142") (pintype "bidirectional"))
    )
    (net (code "159") (name "unconnected-(MCU1-PF0{slash}FSMC_A0{slash}I2C2_SDA-Pad10)") (class "Default")
      (node (ref "MCU1") (pin "10") (pinfunction "PF0/FSMC_A0/I2C2_SDA_10") (pintype "bidirectional"))
    )
    (net (code "160") (name "unconnected-(MCU1-PF1{slash}FSMC_A1{slash}I2C2_SC-Pad11)") (class "Default")
      (node (ref "MCU1") (pin "11") (pinfunction "PF1/FSMC_A1/I2C2_SC_11") (pintype "bidirectional"))
    )
    (net (code "161") (name "unconnected-(MCU1-PF2{slash}FSMC_A2{slash}I2C2_SMBA-Pad12)") (class "Default")
      (node (ref "MCU1") (pin "12") (pinfunction "PF2/FSMC_A2/I2C2_SMBA_12") (pintype "bidirectional"))
    )
    (net (code "162") (name "unconnected-(MCU1-PF3{slash}FSMC_A3<>ADC3_IN9-Pad13)") (class "Default")
      (node (ref "MCU1") (pin "13") (pinfunction "PF3/FSMC_A3<>ADC3_IN9_13") (pintype "bidirectional"))
    )
    (net (code "163") (name "unconnected-(MCU1-PF4{slash}FSMC_A4<>ADC3_IN14-Pad14)") (class "Default")
      (node (ref "MCU1") (pin "14") (pinfunction "PF4/FSMC_A4<>ADC3_IN14_14") (pintype "bidirectional"))
    )
    (net (code "164") (name "unconnected-(MCU1-PF5{slash}FSMC_A5<>ADC3_IN15-Pad15)") (class "Default")
      (node (ref "MCU1") (pin "15") (pinfunction "PF5/FSMC_A5<>ADC3_IN15_15") (pintype "bidirectional"))
    )
    (net (code "165") (name "unconnected-(MCU1-PF6{slash}TIM10_CH1{slash}FSMC_NIORD<>ADC3_IN4-Pad18)") (class "Default")
      (node (ref "MCU1") (pin "18") (pinfunction "PF6/TIM10_CH1/FSMC_NIORD<>ADC3_IN4_18") (pintype "bidirectional"))
    )
    (net (code "166") (name "unconnected-(MCU1-PF7{slash}TIM11_CH1{slash}FSMC_NREG<>ADC3_IN5-Pad19)") (class "Default")
      (node (ref "MCU1") (pin "19") (pinfunction "PF7/TIM11_CH1/FSMC_NREG<>ADC3_IN5_19") (pintype "bidirectional"))
    )
    (net (code "167") (name "unconnected-(MCU1-PF9{slash}TIM14_CH1{slash}FSMC_CD<>ADC3_IN7-Pad21)") (class "Default")
      (node (ref "MCU1") (pin "21") (pinfunction "PF9/TIM14_CH1/FSMC_CD<>ADC3_IN7_21") (pintype "bidirectional"))
    )
    (net (code "168") (name "unconnected-(MCU1-PF10{slash}FSMC_INTR<>ADC3_IN8-Pad22)") (class "Default")
      (node (ref "MCU1") (pin "22") (pinfunction "PF10/FSMC_INTR<>ADC3_IN8_22") (pintype "bidirectional"))
    )
    (net (code "169") (name "unconnected-(MCU1-PF13{slash}FSMC_A7-Pad53)") (class "Default")
      (node (ref "MCU1") (pin "53") (pinfunction "PF13/FSMC_A7_53") (pintype "bidirectional"))
    )
    (net (code "170") (name "unconnected-(MCU1-PF14{slash}FSMC_A8-Pad54)") (class "Default")
      (node (ref "MCU1") (pin "54") (pinfunction "PF14/FSMC_A8_54") (pintype "bidirectional"))
    )
    (net (code "171") (name "unconnected-(MCU1-PF15{slash}FSMC_A9-Pad55)") (class "Default")
      (node (ref "MCU1") (pin "55") (pinfunction "PF15/FSMC_A9_55") (pintype "bidirectional"))
    )
    (net (code "172") (name "unconnected-(MCU1-PG0{slash}FSMC_A10-Pad56)") (class "Default")
      (node (ref "MCU1") (pin "56") (pinfunction "PG0/FSMC_A10_56") (pintype "bidirectional"))
    )
    (net (code "173") (name "unconnected-(MCU1-PG1{slash}FSMC_A11-Pad57)") (class "Default")
      (node (ref "MCU1") (pin "57") (pinfunction "PG1/FSMC_A11_57") (pintype "bidirectional"))
    )
    (net (code "174") (name "unconnected-(MCU1-PG2{slash}FSMC_A12-Pad87)") (class "Default")
      (node (ref "MCU1") (pin "87") (pinfunction "PG2/FSMC_A12_87") (pintype "bidirectional"))
    )
    (net (code "175") (name "unconnected-(MCU1-PG3{slash}FSMC_A13-Pad88)") (class "Default")
      (node (ref "MCU1") (pin "88") (pinfunction "PG3/FSMC_A13_88") (pintype "bidirectional"))
    )
    (net (code "176") (name "unconnected-(MCU1-PG4{slash}FSMC_A14-Pad89)") (class "Default")
      (node (ref "MCU1") (pin "89") (pinfunction "PG4/FSMC_A14_89") (pintype "bidirectional"))
    )
    (net (code "177") (name "unconnected-(MCU1-PG5{slash}FSMC_A15-Pad90)") (class "Default")
      (node (ref "MCU1") (pin "90") (pinfunction "PG5/FSMC_A15_90") (pintype "bidirectional"))
    )
    (net (code "178") (name "unconnected-(MCU1-PG6{slash}FSMC_INT2-Pad91)") (class "Default")
      (node (ref "MCU1") (pin "91") (pinfunction "PG6/FSMC_INT2_91") (pintype "bidirectional"))
    )
    (net (code "179") (name "unconnected-(MCU1-PG7{slash}FSMC_INT3{slash}USART6_CK-Pad92)") (class "Default")
      (node (ref "MCU1") (pin "92") (pinfunction "PG7/FSMC_INT3/USART6_CK_92") (pintype "bidirectional"))
    )
    (net (code "180") (name "unconnected-(MCU1-PG10{slash}FSMC_NCE4_1{slash}FSMC_NE3-Pad125)") (class "Default")
      (node (ref "MCU1") (pin "125") (pinfunction "PG10/FSMC_NCE4_1/FSMC_NE3_125") (pintype "bidirectional"))
    )
    (net (code "181") (name "unconnected-(MCU1-PG11{slash}FSMC_NCE4_2{slash}ETH_MII_TX_EN-Pad126)") (class "Default")
      (node (ref "MCU1") (pin "126") (pinfunction "PG11/FSMC_NCE4_2/ETH_MII_TX_EN_126") (pintype "bidirectional"))
    )
    (net (code "182") (name "unconnected-(MCU1-PG13{slash}FSMC_A24{slash}USART6_CTS{slash}ETH_MII_TXD0{slash}ETH_RMII___TXD0-Pad128)") (class "Default")
      (node (ref "MCU1") (pin "128") (pinfunction "PG13/FSMC_A24/USART6_CTS/ETH_MII_TXD0/ETH_RMII___TXD0_128") (pintype "bidirectional"))
    )
    (net (code "183") (name "unconnected-(MCU1-PG15{slash}USART6_CTS{slash}DCMI_D13-Pad132)") (class "Default")
      (node (ref "MCU1") (pin "132") (pinfunction "PG15/USART6_CTS/DCMI_D13_132") (pintype "bidirectional"))
    )
    (net (code "184") (name "unconnected-(MCU1-{slash}USART6_RTS{slash}ETH_PPS_OUT-Pad93)") (class "Default")
      (node (ref "MCU1") (pin "93") (pinfunction "/USART6_RTS/ETH_PPS_OUT_93") (pintype "bidirectional"))
    )
    (net (code "185") (name "unconnected-(RFID1-IRQ-Pad5)") (class "Default")
      (node (ref "RFID1") (pin "5") (pinfunction "IRQ_5") (pintype "passive"))
    )
    (net (code "186") (name "unconnected-(S1-I{slash}O1-Pad3)") (class "Default")
      (node (ref "S1") (pin "3") (pinfunction "I/O1_3") (pintype "passive"))
    )
    (net (code "187") (name "unconnected-(S1-I{slash}O2-Pad4)") (class "Default")
      (node (ref "S1") (pin "4") (pinfunction "I/O2_4") (pintype "passive"))
    )
    (net (code "188") (name "unconnected-(S1-I{slash}O2-Pad6)") (class "Default")
      (node (ref "S1") (pin "6") (pinfunction "I/O2_6") (pintype "passive"))
    )
    (net (code "189") (name "unconnected-(S1-TAP2-Pad5)") (class "Default")
      (node (ref "S1") (pin "5") (pinfunction "TAP2_5") (pintype "passive"))
    )
    (net (code "190") (name "unconnected-(U2-OUT-Pad4)") (class "Default")
      (node (ref "U2") (pin "4") (pinfunction "OUT_4") (pintype "passive"))
    )
    (net (code "191") (name "unconnected-(sdcard1-CK-OUT-Pad10)") (class "Default")
      (node (ref "sdcard1") (pin "10") (pinfunction "CK-OUT_10") (pintype "passive"))
    )
  )
)
